# amplifier.net
KiCad netlist of a schematic drawn in Altium Designer
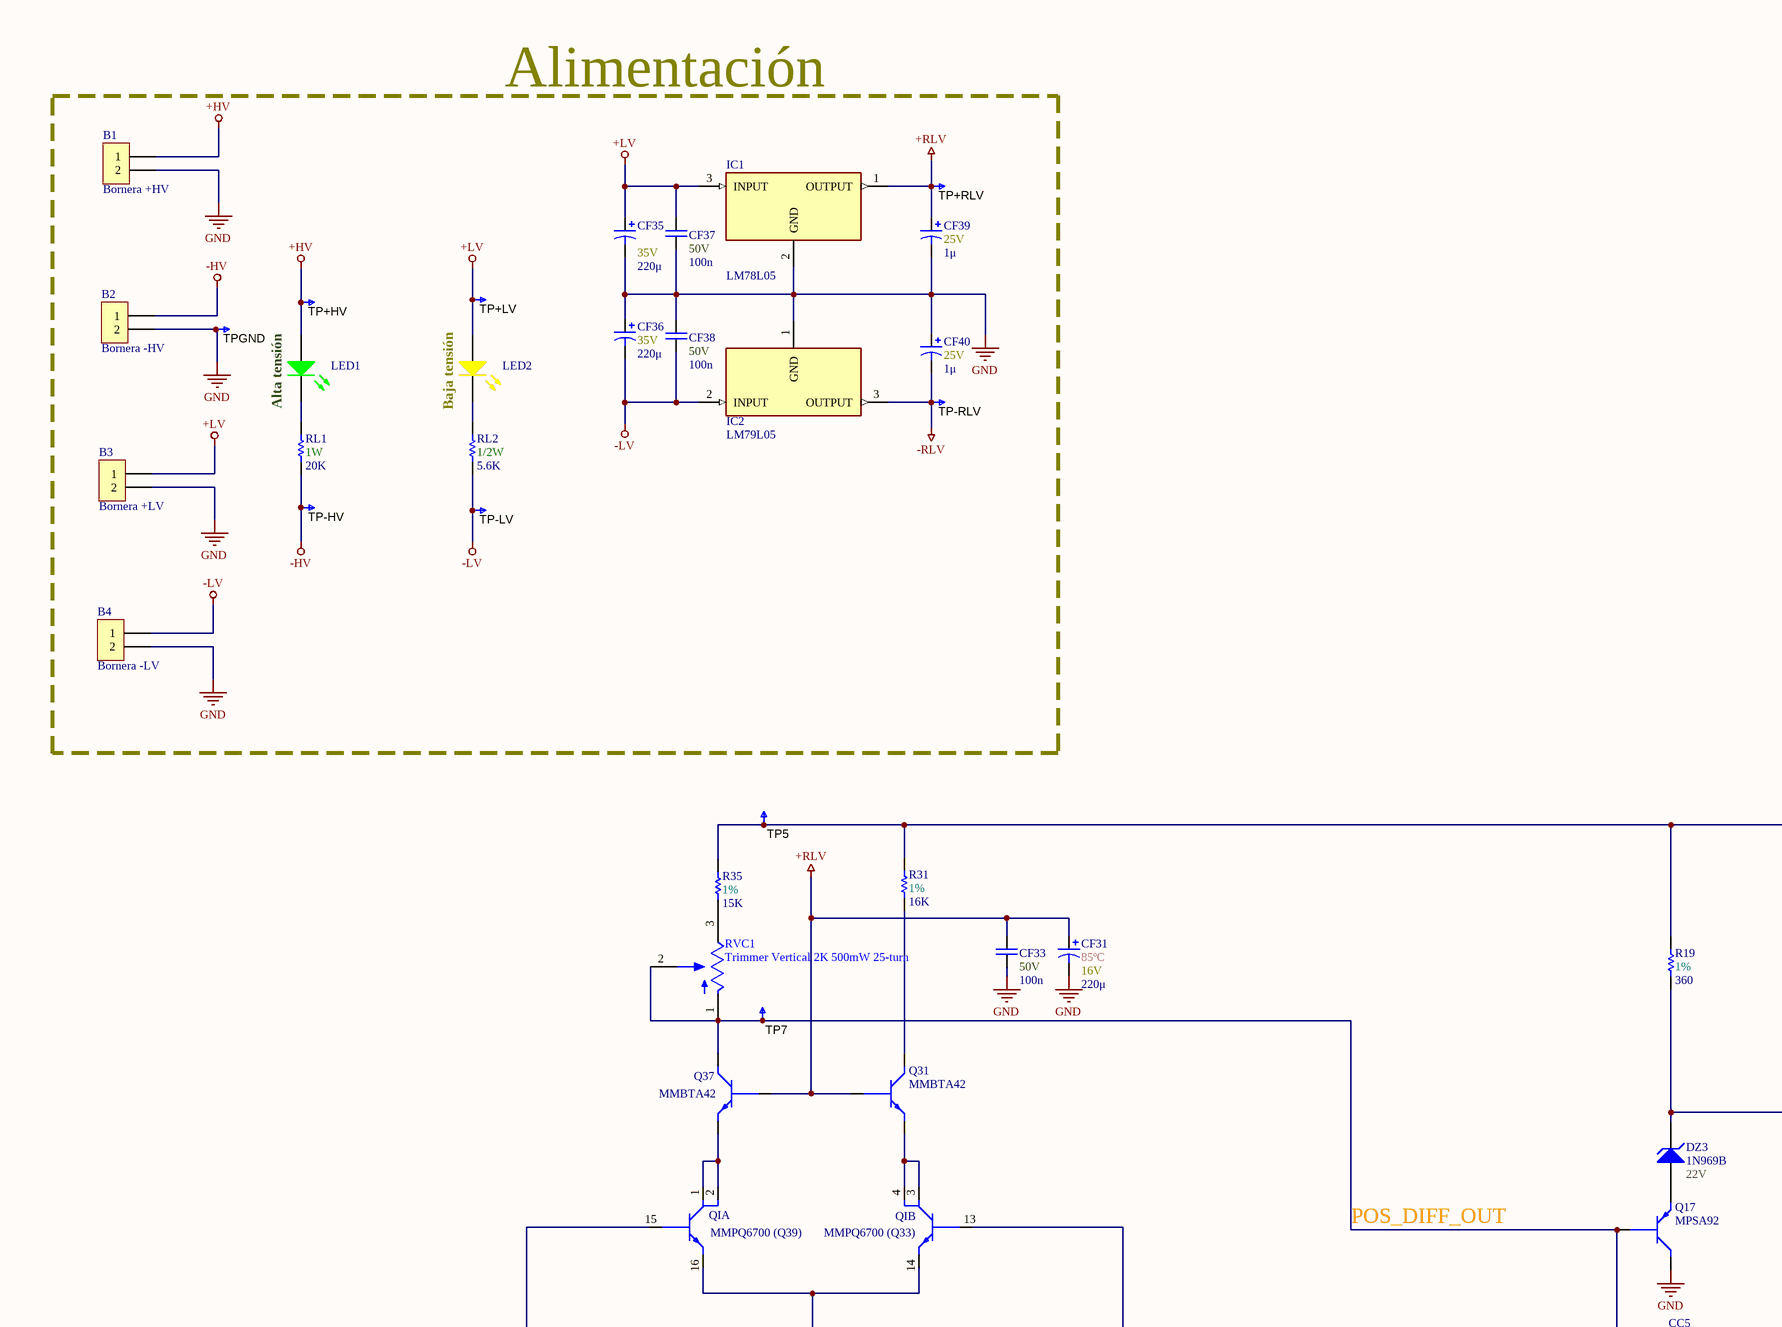
[diagram p0: amplifier.SchDoc, top left]
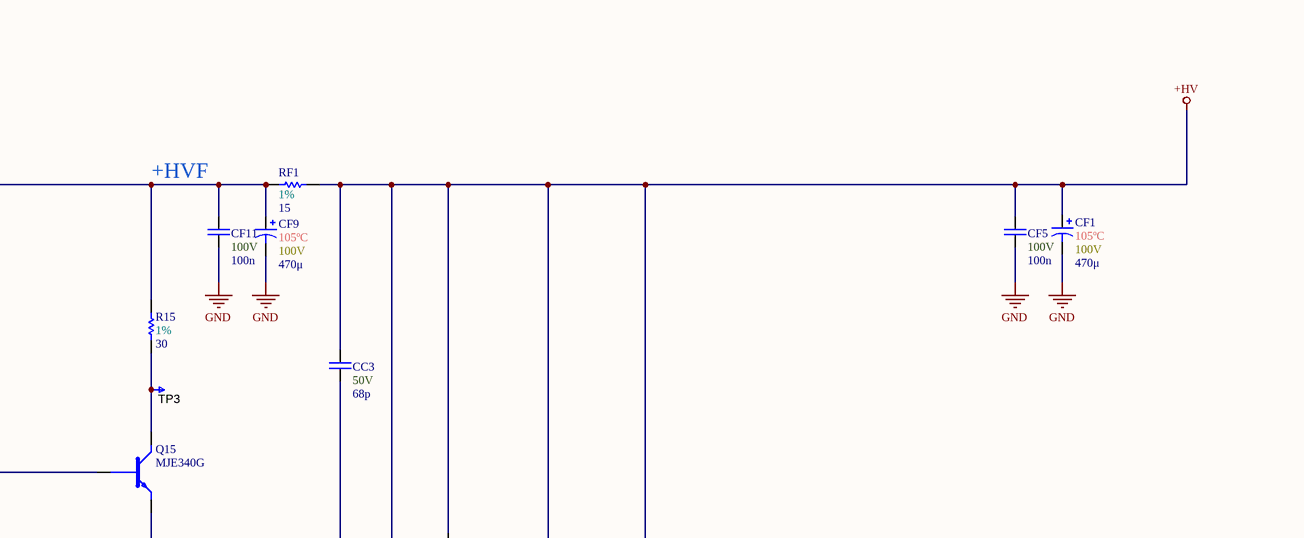
[diagram p1: amplifier.SchDoc, top right]
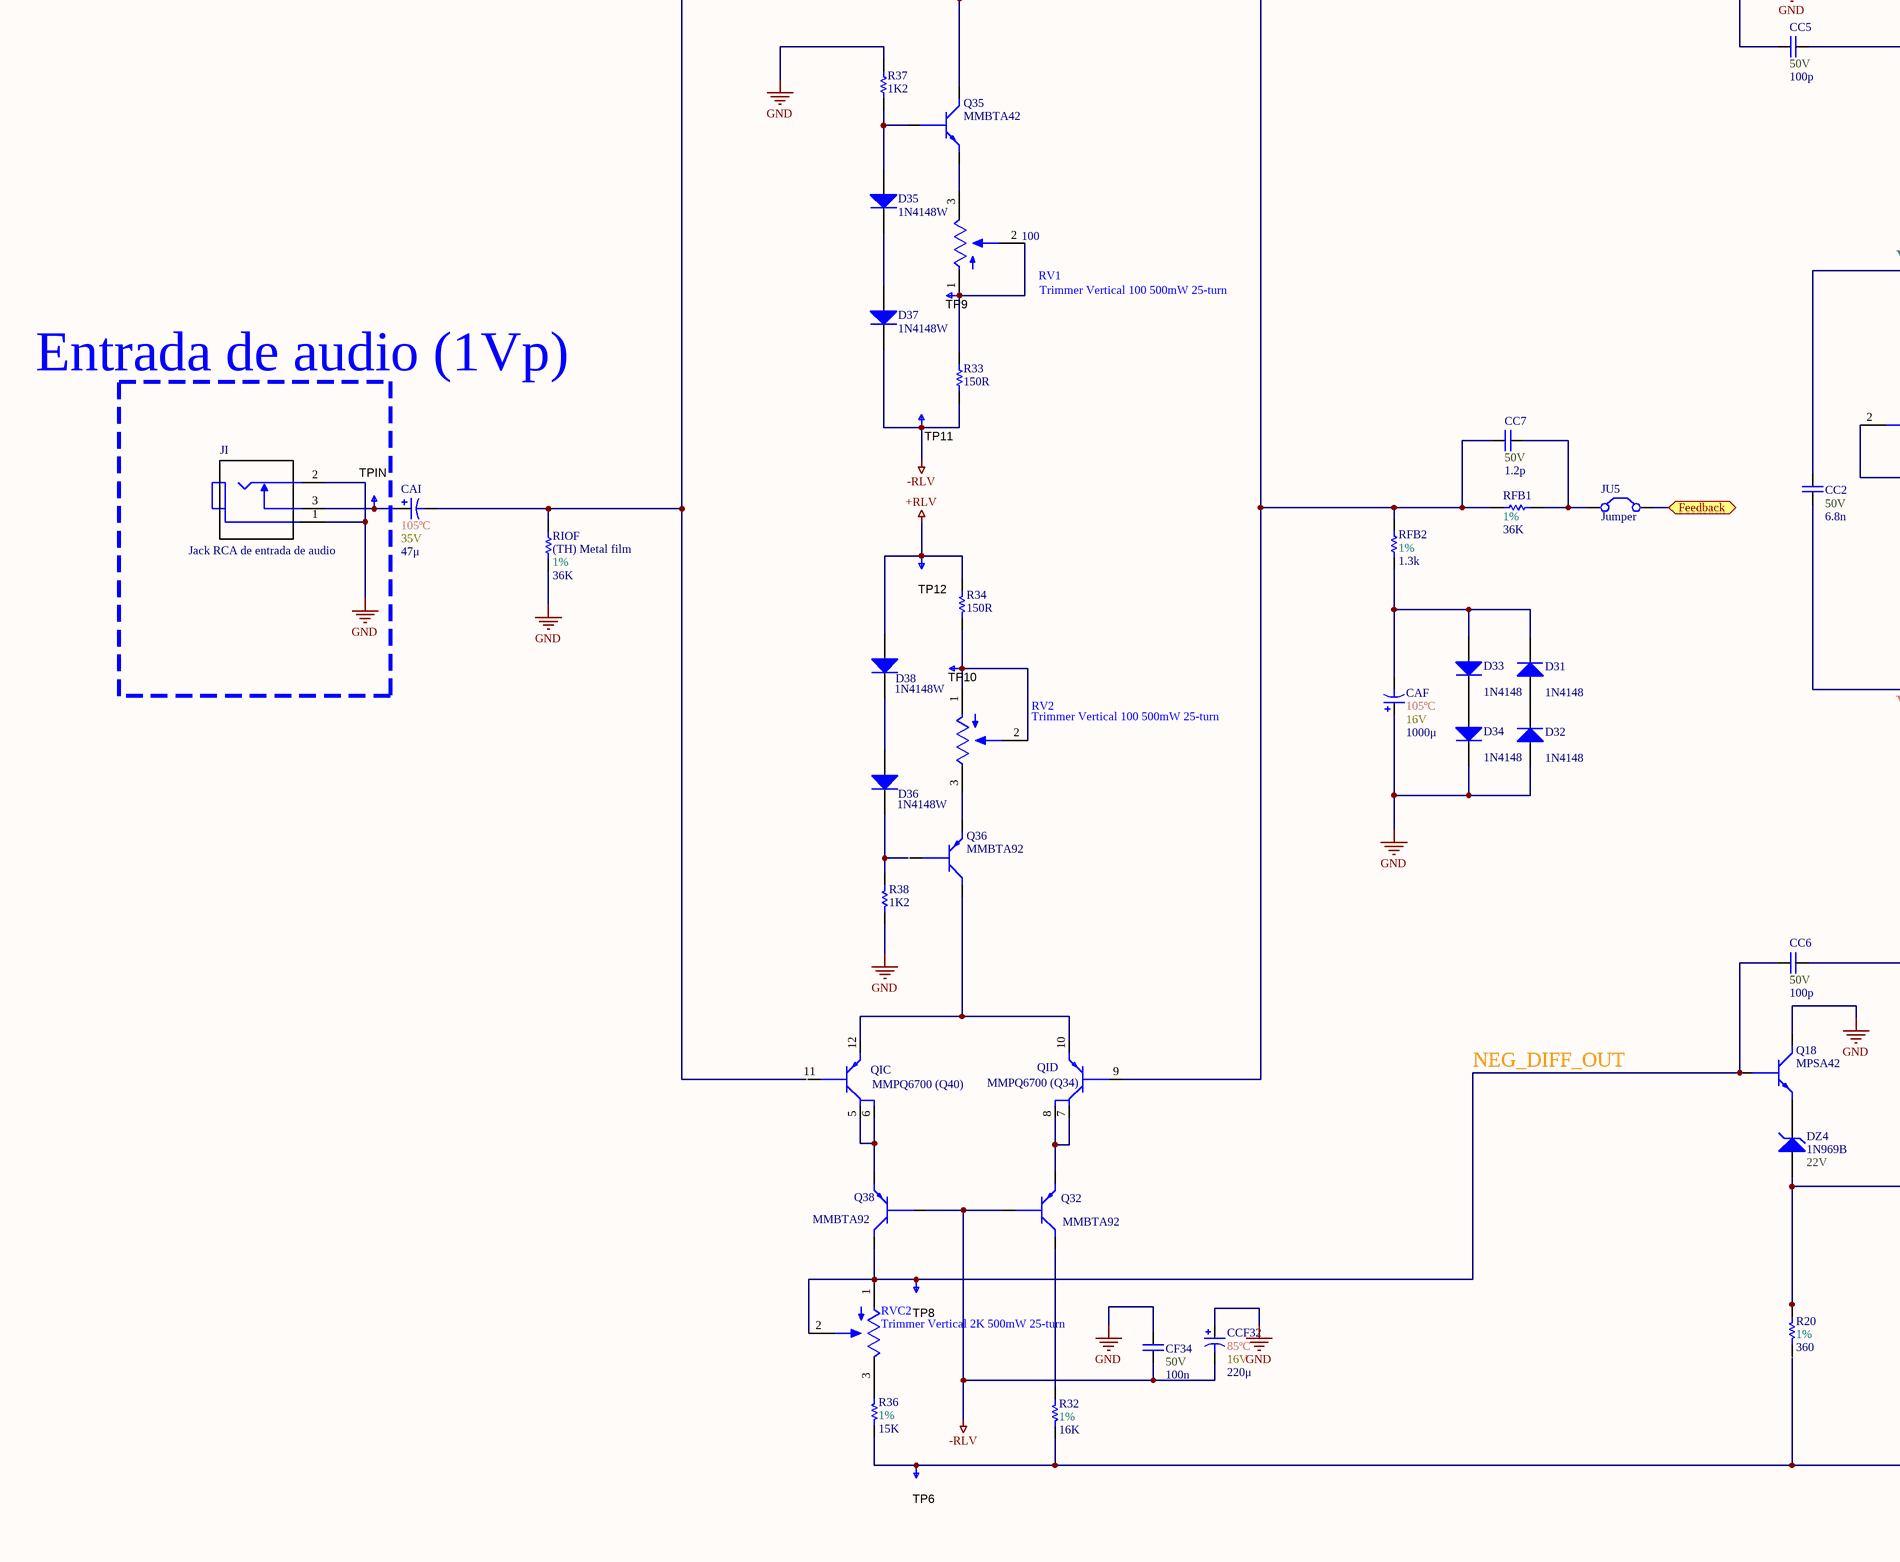
[diagram p2: amplifier.SchDoc, bottom left]
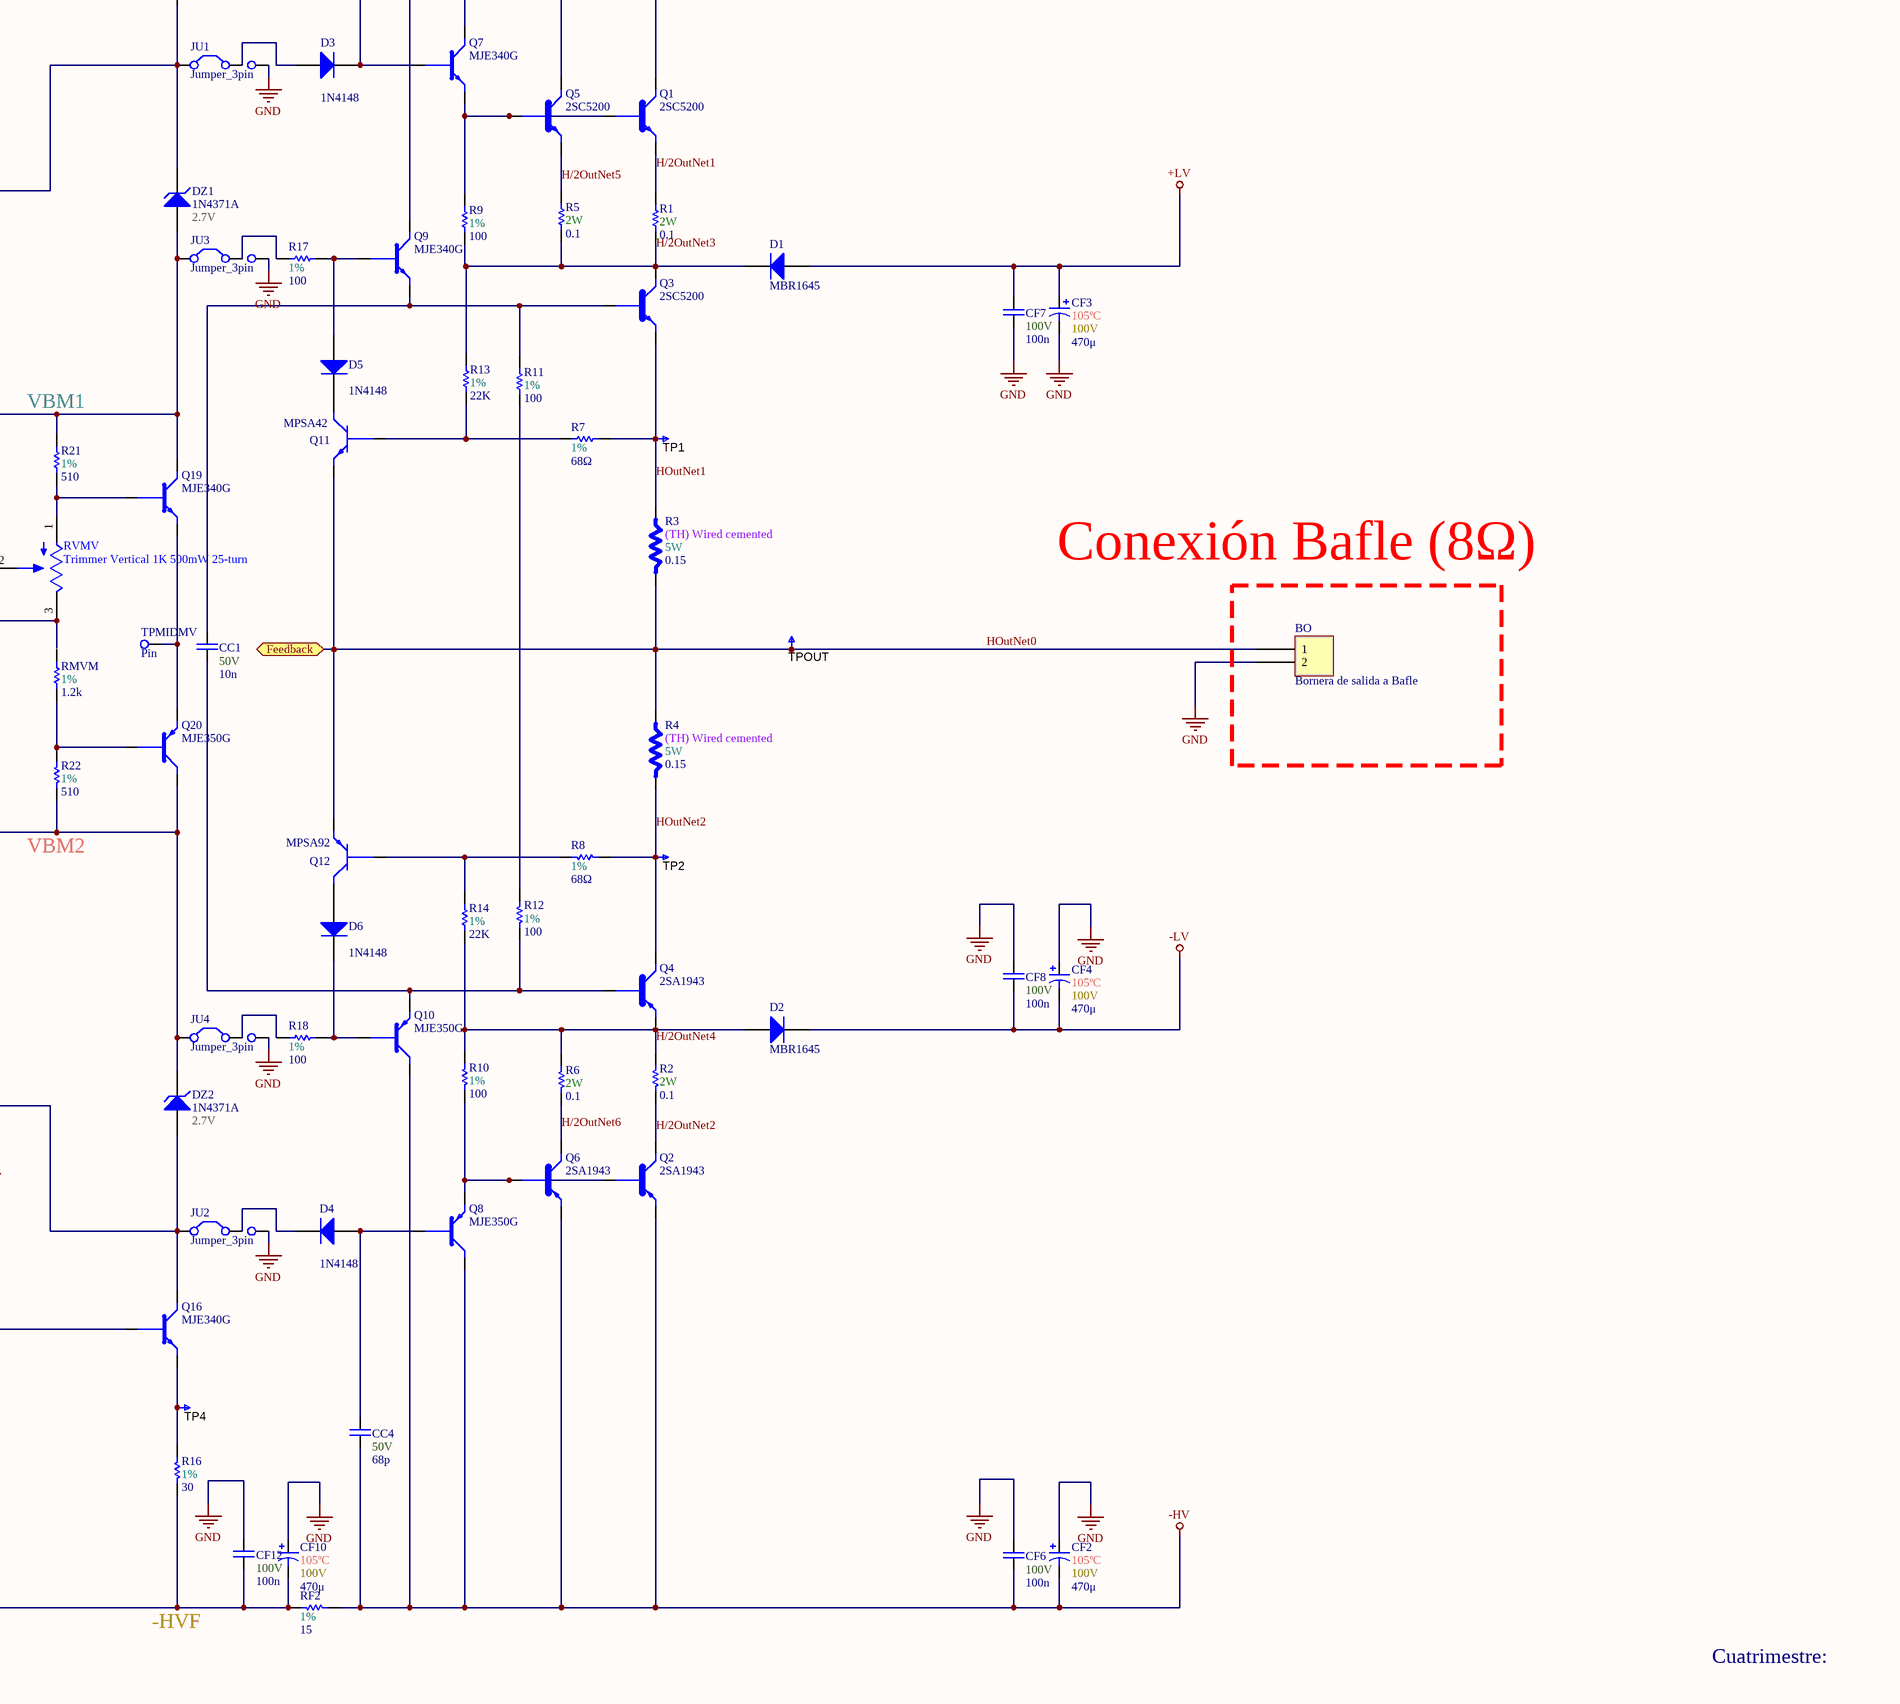
[diagram p3: amplifier.SchDoc, bottom right]

(export (version "E")
  (design (tool "Eeschema 10.0.6"))
  (components
    (comp (ref "B1")
      (value "Bornera +HV")
      (footprint "TE-C-282822-2-C-PLUGGED")
      (description "TERMI-BLOK HEADER,ASSY90 2P - serie 282822 - 5.00mm")
      (fields (field (name "MANUFACTURER") "TE Connectivity") (field (name "PARTNO") "C-282822-2-C"))
      (libsource (lib "Connectors") (part "C-282822-2-C"))
    )
    (comp (ref "B2")
      (value "Bornera -HV")
      (footprint "TE-C-282822-2-C-PLUGGED")
      (description "TERMI-BLOK HEADER,ASSY90 2P - serie 282822 - 5.00mm")
      (fields (field (name "MANUFACTURER") "TE Connectivity") (field (name "PARTNO") "C-282822-2-C"))
      (libsource (lib "Connectors") (part "C-282822-2-C"))
    )
    (comp (ref "B3")
      (value "Bornera +LV")
      (footprint "TE-C-282822-2-C-PLUGGED")
      (description "TERMI-BLOK HEADER,ASSY90 2P - serie 282822 - 5.00mm")
      (fields (field (name "MANUFACTURER") "TE Connectivity") (field (name "PARTNO") "C-282822-2-C"))
      (libsource (lib "Connectors") (part "C-282822-2-C"))
    )
    (comp (ref "B4")
      (value "Bornera -LV")
      (footprint "TE-C-282822-2-C-PLUGGED")
      (description "TERMI-BLOK HEADER,ASSY90 2P - serie 282822 - 5.00mm")
      (fields (field (name "MANUFACTURER") "TE Connectivity") (field (name "PARTNO") "C-282822-2-C"))
      (libsource (lib "Connectors") (part "C-282822-2-C"))
    )
    (comp (ref "BO")
      (value "Bornera de salida a Bafle")
      (footprint "TE 8PCV-02-006")
      (description "TE Barrier Terminal Block, 2P")
      (fields (field (name "VOLTAGE") "600V"))
      (libsource (lib "Connectors") (part "8PCV-02-006"))
    )
    (comp (ref "CAF")
      (value "1000μ")
      (footprint "Al. Electrolytic 10.0mmx17.0mmx5.0mm-CLEAN")
      (description "Aluminum Electrolytic Capacitor 1000μF 16V 20% 105º")
      (fields
        (field (name "TOLERANCE") "20%")
        (field (name "TEMPERATURE") "105ºC")
        (field (name "VOLTAGE") "16V")
        (field (name "Comment") "Al. Elect. 1000u 16V 20% 105º")
      )
      (libsource (lib "Capacitors") (part "Al. Elect. 1000u 16V 20% 105º"))
    )
    (comp (ref "CAI")
      (value "47μ")
      (footprint "Al. Electrolytic 6.3mmx11.0mmx2.5mm-CLEAN")
      (description "Aluminum Electrolytic Capacitor 47μF 35V 20% 105º")
      (fields
        (field (name "TOLERANCE") "20%")
        (field (name "TEMPERATURE") "105ºC")
        (field (name "VOLTAGE") "35V")
        (field (name "Comment") "Al. Elect. 47u 35V 20% 105º")
      )
      (libsource (lib "Capacitors") (part "Al. Elect. 47u 35V 20% 105º"))
    )
    (comp (ref "CC1")
      (value "10n")
      (footprint "Cer. pitch 5.0mm height 5.5mm")
      (description "Ceramic Capacitor 10nF 50V 10%")
      (fields
        (field (name "TOLERANCE") "10%")
        (field (name "VOLTAGE") "50V")
        (field (name "Comment") "Cer. 10n 50V 10%")
      )
      (libsource (lib "Capacitors") (part "Cer. 10n 50V 10%"))
    )
    (comp (ref "CC2")
      (value "6.8n")
      (footprint "Cer. pitch 2.5mm height 5.0mm")
      (description "Ceramic Capacitor 6.8nF 50V 10%")
      (fields
        (field (name "TOLERANCE") "10%")
        (field (name "VOLTAGE") "50V")
        (field (name "Comment") "Cer. 6.8n 50V 10%")
      )
      (libsource (lib "Capacitors") (part "Cer. 6.8n 50V 10%"))
    )
    (comp (ref "CC3")
      (value "68p")
      (footprint "Cer. pitch 5.08mm height 6.00mm")
      (description "Ceramic Capacitor 68pF 50V 10%")
      (fields
        (field (name "TOLERANCE") "10%")
        (field (name "VOLTAGE") "50V")
        (field (name "Comment") "Cer. 68p 50V 10%")
      )
      (libsource (lib "Capacitors") (part "Cer. 68p 50V 10%"))
    )
    (comp (ref "CC4")
      (value "68p")
      (footprint "Cer. pitch 5.08mm height 6.00mm")
      (description "Ceramic Capacitor 68pF 50V 10%")
      (fields
        (field (name "TOLERANCE") "10%")
        (field (name "VOLTAGE") "50V")
        (field (name "Comment") "Cer. 68p 50V 10%")
      )
      (libsource (lib "Capacitors") (part "Cer. 68p 50V 10%"))
    )
    (comp (ref "CC5")
      (value "100p")
      (footprint "Cer. pitch 5.08mm height 6.00mm")
      (description "Ceramic Capacitor 100pF 50V 10%")
      (fields
        (field (name "TOLERANCE") "10%")
        (field (name "VOLTAGE") "50V")
        (field (name "Comment") "Cer. 100p 50V 10%")
      )
      (libsource (lib "Capacitors") (part "Cer. 100p 50V 10%"))
    )
    (comp (ref "CC6")
      (value "100p")
      (footprint "Cer. pitch 5.08mm height 6.00mm")
      (description "Ceramic Capacitor 100pF 50V 10%")
      (fields
        (field (name "TOLERANCE") "10%")
        (field (name "VOLTAGE") "50V")
        (field (name "Comment") "Cer. 100p 50V 10%")
      )
      (libsource (lib "Capacitors") (part "Cer. 100p 50V 10%"))
    )
    (comp (ref "CC7")
      (value "1.2p")
      (footprint "Cer. pitch 5.08mm height 6.00mm")
      (description "Ceramic Capacitor 1.2pF 50V 10%")
      (fields
        (field (name "TOLERANCE") "10%")
        (field (name "VOLTAGE") "50V")
        (field (name "Comment") "Cer. 1.2p 50V 10%")
      )
      (libsource (lib "Capacitors") (part "Cer. 1.2p 50V 10%"))
    )
    (comp (ref "CCF32")
      (value "220μ")
      (footprint "Al. Electrolytic 6.3mmx12.0mmx2.5mm-CLEAN")
      (description "Aluminum Electrolytic Capacitor 220μF 16V 20% 85º")
      (fields
        (field (name "TOLERANCE") "20%")
        (field (name "TEMPERATURE") "85ºC")
        (field (name "VOLTAGE") "16V")
        (field (name "Comment") "Al. Elect. 220u 16V 20% 85º")
      )
      (libsource (lib "Capacitors") (part "Al. Elect. 220u 16V 20% 85º"))
    )
    (comp (ref "CF1")
      (value "470μ")
      (footprint "Al. Electrolytic 16.0mmx33.0mmx7.5mm-CLEAN")
      (description "Aluminum Electrolytic Capacitor 470μF 100V 20% 105º")
      (fields
        (field (name "TOLERANCE") "20%")
        (field (name "TEMPERATURE") "105ºC")
        (field (name "VOLTAGE") "100V")
        (field (name "Comment") "Al. Elect. 470u 100V 20% 105º")
      )
      (libsource (lib "Capacitors") (part "Al. Elect. 470u 100V 20% 105º"))
    )
    (comp (ref "CF2")
      (value "470μ")
      (footprint "Al. Electrolytic 16.0mmx33.0mmx7.5mm-CLEAN")
      (description "Aluminum Electrolytic Capacitor 470μF 100V 20% 105º")
      (fields
        (field (name "TOLERANCE") "20%")
        (field (name "TEMPERATURE") "105ºC")
        (field (name "VOLTAGE") "100V")
        (field (name "Comment") "Al. Elect. 470u 100V 20% 105º")
      )
      (libsource (lib "") (part "Al. Elect. 470u 100V 20% 105º_1"))
    )
    (comp (ref "CF3")
      (value "470μ")
      (footprint "Al. Electrolytic 16.0mmx33.0mmx7.5mm-CLEAN")
      (description "Aluminum Electrolytic Capacitor 470μF 100V 20% 105º")
      (fields
        (field (name "TOLERANCE") "20%")
        (field (name "TEMPERATURE") "105ºC")
        (field (name "VOLTAGE") "100V")
        (field (name "Comment") "Al. Elect. 470u 100V 20% 105º")
      )
      (libsource (lib "Capacitors") (part "Al. Elect. 470u 100V 20% 105º"))
    )
    (comp (ref "CF4")
      (value "470μ")
      (footprint "Al. Electrolytic 16.0mmx33.0mmx7.5mm-CLEAN")
      (description "Aluminum Electrolytic Capacitor 470μF 100V 20% 105º")
      (fields
        (field (name "TOLERANCE") "20%")
        (field (name "TEMPERATURE") "105ºC")
        (field (name "VOLTAGE") "100V")
        (field (name "Comment") "Al. Elect. 470u 100V 20% 105º")
      )
      (libsource (lib "") (part "Al. Elect. 470u 100V 20% 105º_1"))
    )
    (comp (ref "CF5")
      (value "100n")
      (footprint "Cer. pitch 5.0mm height 6.6mm")
      (description "Polyester Capacitor 100nF 100V 10%")
      (fields
        (field (name "TOLERANCE") "10%")
        (field (name "VOLTAGE") "100V")
        (field (name "Comment") "Poly. 100n 100V 10%")
      )
      (libsource (lib "Capacitors") (part "Poly. 100n 100V 10%"))
    )
    (comp (ref "CF6")
      (value "100n")
      (footprint "Cer. pitch 5.0mm height 6.6mm")
      (description "Polyester Capacitor 100nF 100V 10%")
      (fields
        (field (name "TOLERANCE") "10%")
        (field (name "VOLTAGE") "100V")
        (field (name "Comment") "Poly. 100n 100V 10%")
      )
      (libsource (lib "Capacitors") (part "Poly. 100n 100V 10%"))
    )
    (comp (ref "CF7")
      (value "100n")
      (footprint "Cer. pitch 5.0mm height 6.6mm")
      (description "Polyester Capacitor 100nF 100V 10%")
      (fields
        (field (name "TOLERANCE") "10%")
        (field (name "VOLTAGE") "100V")
        (field (name "Comment") "Poly. 100n 100V 10%")
      )
      (libsource (lib "Capacitors") (part "Poly. 100n 100V 10%"))
    )
    (comp (ref "CF8")
      (value "100n")
      (footprint "Cer. pitch 5.0mm height 6.6mm")
      (description "Polyester Capacitor 100nF 100V 10%")
      (fields
        (field (name "TOLERANCE") "10%")
        (field (name "VOLTAGE") "100V")
        (field (name "Comment") "Poly. 100n 100V 10%")
      )
      (libsource (lib "Capacitors") (part "Poly. 100n 100V 10%"))
    )
    (comp (ref "CF9")
      (value "470μ")
      (footprint "Al. Electrolytic 16.0mmx33.0mmx7.5mm-CLEAN")
      (description "Aluminum Electrolytic Capacitor 470μF 100V 20% 105º")
      (fields
        (field (name "TOLERANCE") "20%")
        (field (name "TEMPERATURE") "105ºC")
        (field (name "VOLTAGE") "100V")
        (field (name "Comment") "Al. Elect. 470u 100V 20% 105º")
      )
      (libsource (lib "Capacitors") (part "Al. Elect. 470u 100V 20% 105º"))
    )
    (comp (ref "CF10")
      (value "470μ")
      (footprint "Al. Electrolytic 16.0mmx33.0mmx7.5mm-CLEAN")
      (description "Aluminum Electrolytic Capacitor 470μF 100V 20% 105º")
      (fields
        (field (name "TOLERANCE") "20%")
        (field (name "TEMPERATURE") "105ºC")
        (field (name "VOLTAGE") "100V")
        (field (name "Comment") "Al. Elect. 470u 100V 20% 105º")
      )
      (libsource (lib "") (part "Al. Elect. 470u 100V 20% 105º_1"))
    )
    (comp (ref "CF11")
      (value "100n")
      (footprint "Cer. pitch 5.0mm height 6.6mm")
      (description "Polyester Capacitor 100nF 100V 10%")
      (fields
        (field (name "TOLERANCE") "10%")
        (field (name "VOLTAGE") "100V")
        (field (name "Comment") "Poly. 100n 100V 10%")
      )
      (libsource (lib "Capacitors") (part "Poly. 100n 100V 10%"))
    )
    (comp (ref "CF12")
      (value "100n")
      (footprint "Cer. pitch 5.0mm height 6.6mm")
      (description "Polyester Capacitor 100nF 100V 10%")
      (fields
        (field (name "TOLERANCE") "10%")
        (field (name "VOLTAGE") "100V")
        (field (name "Comment") "Poly. 100n 100V 10%")
      )
      (libsource (lib "Capacitors") (part "Poly. 100n 100V 10%"))
    )
    (comp (ref "CF31")
      (value "220μ")
      (footprint "Al. Electrolytic 6.3mmx12.0mmx2.5mm-CLEAN")
      (description "Aluminum Electrolytic Capacitor 220μF 16V 20% 85º")
      (fields
        (field (name "TOLERANCE") "20%")
        (field (name "TEMPERATURE") "85ºC")
        (field (name "VOLTAGE") "16V")
        (field (name "Comment") "Al. Elect. 220u 16V 20% 85º")
      )
      (libsource (lib "") (part "Al. Elect. 220u 16V 20% 85º_1"))
    )
    (comp (ref "CF33")
      (value "100n")
      (footprint "Cer. pitch 5.0mm height 5.5mm")
      (description "Ceramic Capacitor 100nF 50V 10%")
      (fields
        (field (name "TOLERANCE") "10%")
        (field (name "VOLTAGE") "50V")
        (field (name "Comment") "Cer. 100n 50V 10%")
      )
      (libsource (lib "Capacitors") (part "Cer. 100n 50V 10%"))
    )
    (comp (ref "CF34")
      (value "100n")
      (footprint "Cer. pitch 5.0mm height 5.5mm")
      (description "Ceramic Capacitor 100nF 50V 10%")
      (fields
        (field (name "TOLERANCE") "10%")
        (field (name "VOLTAGE") "50V")
        (field (name "Comment") "Cer. 100n 50V 10%")
      )
      (libsource (lib "Capacitors") (part "Cer. 100n 50V 10%"))
    )
    (comp (ref "CF35")
      (value "220μ")
      (footprint "Al. Electrolytic 8.0mmx13.0mmx3.5mm-CLEAN")
      (description "Aluminum Electrolytic Capacitor 220μF 35V 20% 105º")
      (fields
        (field (name "TOLERANCE") "20%")
        (field (name "VOLTAGE") "35V")
        (field (name "Comment") "Al. Elect. 220u 35V 20% 105º")
      )
      (libsource (lib "Capacitors") (part "Al. Elect. 220u 35V 20% 105º"))
    )
    (comp (ref "CF36")
      (value "220μ")
      (footprint "Al. Electrolytic 8.0mmx13.0mmx3.5mm-CLEAN")
      (description "Aluminum Electrolytic Capacitor 220μF 35V 20% 105º")
      (fields
        (field (name "TOLERANCE") "20%")
        (field (name "VOLTAGE") "35V")
        (field (name "Comment") "Al. Elect. 220u 35V 20% 105º")
      )
      (libsource (lib "Capacitors") (part "Al. Elect. 220u 35V 20% 105º"))
    )
    (comp (ref "CF37")
      (value "100n")
      (footprint "Cer. pitch 5.0mm height 5.5mm")
      (description "Ceramic Capacitor 100nF 50V 10%")
      (fields
        (field (name "TOLERANCE") "10%")
        (field (name "VOLTAGE") "50V")
        (field (name "Comment") "Cer. 100n 50V 10%")
      )
      (libsource (lib "Capacitors") (part "Cer. 100n 50V 10%"))
    )
    (comp (ref "CF38")
      (value "100n")
      (footprint "Cer. pitch 5.0mm height 5.5mm")
      (description "Ceramic Capacitor 100nF 50V 10%")
      (fields
        (field (name "TOLERANCE") "10%")
        (field (name "VOLTAGE") "50V")
        (field (name "Comment") "Cer. 100n 50V 10%")
      )
      (libsource (lib "Capacitors") (part "Cer. 100n 50V 10%"))
    )
    (comp (ref "CF39")
      (value "1μ")
      (footprint "Tantalum Electrolytic 4.5mmx8.0mmx0.254mm-CLEAN")
      (description "Tantalum Electrolytic Capacitor 1μF 25V 10%")
      (fields
        (field (name "TOLERANCE") "10%")
        (field (name "VOLTAGE") "25V")
        (field (name "Comment") "Tant. Elect. 1u 25V 10%")
      )
      (libsource (lib "Capacitors") (part "Tant. Elect. 1u 25V 10%"))
    )
    (comp (ref "CF40")
      (value "1μ")
      (footprint "Tantalum Electrolytic 4.5mmx8.0mmx0.254mm-CLEAN")
      (description "Tantalum Electrolytic Capacitor 1μF 25V 10%")
      (fields
        (field (name "TOLERANCE") "10%")
        (field (name "VOLTAGE") "25V")
        (field (name "Comment") "Tant. Elect. 1u 25V 10%")
      )
      (libsource (lib "Capacitors") (part "Tant. Elect. 1u 25V 10%"))
    )
    (comp (ref "D1")
      (value "MBR1645")
      (footprint "ONSC-TO-220-2-221B-04")
      (description "45 V, 16 A SWITCHMODE(TM) Schottky Power Rectifier, 2-Pin TO-220, Pb-Free, Tube")
      (libsource (lib "ON Semi Rectifiers") (part "MBR1645"))
    )
    (comp (ref "D2")
      (value "MBR1645")
      (footprint "ONSC-TO-220-2-221B-04")
      (description "45 V, 16 A SWITCHMODE(TM) Schottky Power Rectifier, 2-Pin TO-220, Pb-Free, Tube")
      (libsource (lib "ON Semi Rectifiers") (part "MBR1645"))
    )
    (comp (ref "D3")
      (value "1N4148")
      (footprint "DO-35-0.3mil")
      (description "FAST SWITCHING DIODE")
      (fields
        (field (name "MANUFACTURER") "ON Semiconductors")
        (field (name "POWER") "400mW")
        (field (name "PARTNUMBER") "1N4148")
      )
      (libsource (lib "ON Semi Rectifiers") (part "1N4148"))
    )
    (comp (ref "D4")
      (value "1N4148")
      (footprint "DO-35-0.3mil")
      (description "FAST SWITCHING DIODE")
      (fields
        (field (name "MANUFACTURER") "ON Semiconductors")
        (field (name "POWER") "400mW")
        (field (name "PARTNUMBER") "1N4148")
      )
      (libsource (lib "ON Semi Rectifiers") (part "1N4148"))
    )
    (comp (ref "D5")
      (value "~")
      (footprint "DO-35-0.3mil")
      (description "FAST SWITCHING DIODE")
      (fields
        (field (name "MANUFACTURER") "ON Semiconductors")
        (field (name "POWER") "400mW")
        (field (name "PARTNUMBER") "1N4148")
      )
      (libsource (lib "ON Semi Rectifiers") (part "1N4148"))
    )
    (comp (ref "D6")
      (value "~")
      (footprint "DO-35-0.3mil")
      (description "FAST SWITCHING DIODE")
      (fields
        (field (name "MANUFACTURER") "ON Semiconductors")
        (field (name "POWER") "400mW")
        (field (name "PARTNUMBER") "1N4148")
      )
      (libsource (lib "ON Semi Rectifiers") (part "1N4148"))
    )
    (comp (ref "D31")
      (value "~")
      (footprint "DO-35-0.3mil")
      (description "FAST SWITCHING DIODE")
      (fields
        (field (name "MANUFACTURER") "ON Semiconductors")
        (field (name "POWER") "400mW")
        (field (name "PARTNUMBER") "1N4148")
      )
      (libsource (lib "ON Semi Rectifiers") (part "1N4148"))
    )
    (comp (ref "D32")
      (value "~")
      (footprint "DO-35-0.3mil")
      (description "FAST SWITCHING DIODE")
      (fields
        (field (name "MANUFACTURER") "ON Semiconductors")
        (field (name "POWER") "400mW")
        (field (name "PARTNUMBER") "1N4148")
      )
      (libsource (lib "ON Semi Rectifiers") (part "1N4148"))
    )
    (comp (ref "D33")
      (value "~")
      (footprint "DO-35-0.3mil")
      (description "FAST SWITCHING DIODE")
      (fields
        (field (name "MANUFACTURER") "ON Semiconductors")
        (field (name "POWER") "400mW")
        (field (name "PARTNUMBER") "1N4148")
      )
      (libsource (lib "ON Semi Rectifiers") (part "1N4148"))
    )
    (comp (ref "D34")
      (value "~")
      (footprint "DO-35-0.3mil")
      (description "FAST SWITCHING DIODE")
      (fields
        (field (name "MANUFACTURER") "ON Semiconductors")
        (field (name "POWER") "400mW")
        (field (name "PARTNUMBER") "1N4148")
      )
      (libsource (lib "ON Semi Rectifiers") (part "1N4148"))
    )
    (comp (ref "D35")
      (value "1N4148W")
      (footprint "SOD-123")
      (description "SURFACE MOUNT FAST SWITCHING DIODE")
      (fields (field (name "MANUFACTURER") "Diodes Incorporated") (field (name "POWER") "400mW"))
      (libsource (lib "DIODES_INCROPORATED") (part "1N4148W"))
    )
    (comp (ref "D36")
      (value "1N4148W")
      (footprint "SOD-123")
      (description "SURFACE MOUNT FAST SWITCHING DIODE")
      (fields (field (name "MANUFACTURER") "Diodes Incorporated") (field (name "POWER") "400mW"))
      (libsource (lib "DIODES_INCROPORATED") (part "1N4148W"))
    )
    (comp (ref "D37")
      (value "1N4148W")
      (footprint "SOD-123")
      (description "SURFACE MOUNT FAST SWITCHING DIODE")
      (fields (field (name "MANUFACTURER") "Diodes Incorporated") (field (name "POWER") "400mW"))
      (libsource (lib "DIODES_INCROPORATED") (part "1N4148W"))
    )
    (comp (ref "D38")
      (value "1N4148W")
      (footprint "SOD-123")
      (description "SURFACE MOUNT FAST SWITCHING DIODE")
      (fields (field (name "MANUFACTURER") "Diodes Incorporated") (field (name "POWER") "400mW"))
      (libsource (lib "DIODES_INCROPORATED") (part "1N4148W"))
    )
    (comp (ref "DZ1")
      (value "1N4371A")
      (footprint "DO-35-0.3mil")
      (description "Zener Diode, 2.7V, 500mW")
      (fields
        (field (name "MANUFACTURER") "Microsemi")
        (field (name "POWER") "500mW")
        (field (name "ZV") "2.7V")
        (field (name "PUBLISHER") "Altium Limited")
      )
      (libsource (lib "MICROSEMI") (part "1N4371A"))
    )
    (comp (ref "DZ2")
      (value "1N4371A")
      (footprint "DO-35-0.3mil")
      (description "Zener Diode, 2.7V, 500mW")
      (fields
        (field (name "MANUFACTURER") "Microsemi")
        (field (name "POWER") "500mW")
        (field (name "ZV") "2.7V")
        (field (name "PUBLISHER") "Altium Limited")
      )
      (libsource (lib "MICROSEMI") (part "1N4371A"))
    )
    (comp (ref "DZ3")
      (value "1N969B")
      (footprint "DO-35-0.3mil")
      (description "Zener Diode, 22V, 500mW")
      (fields
        (field (name "MANUFACTURER") "Microsemi")
        (field (name "POWER") "500mW")
        (field (name "ZV") "22V")
        (field (name "PUBLISHER") "Altium Limited")
      )
      (libsource (lib "MICROSEMI") (part "1N969B"))
    )
    (comp (ref "DZ4")
      (value "1N969B")
      (footprint "DO-35-0.3mil")
      (description "Zener Diode, 22V, 500mW")
      (fields
        (field (name "MANUFACTURER") "Microsemi")
        (field (name "POWER") "500mW")
        (field (name "ZV") "22V")
        (field (name "PUBLISHER") "Altium Limited")
      )
      (libsource (lib "MICROSEMI") (part "1N969B"))
    )
    (comp (ref "IC1")
      (value "LM78L05")
      (footprint "TO-92-1")
      (description "5V fixed regulator - 100mA")
      (fields (field (name "MANUFACTURER_PART_NUMBER") "LM7805"))
      (libsource (lib "FIXED_REGULATORS") (part "LM78L05"))
    )
    (comp (ref "IC2")
      (value "LM79L05")
      (footprint "TO-92-1")
      (description "-5V fixed regulator - 100mA")
      (fields (field (name "MANUFACTURER_PART_NUMBER") "LM7805"))
      (libsource (lib "FIXED_REGULATORS") (part "LM79L05"))
    )
    (comp (ref "JI")
      (value "Jack RCA de entrada de audio")
      (footprint "*SWITCHCRAFT_PJRAN1X1U01X")
      (description "Conn Phono Jack F 3 POS Solder RA Thru-Hole 3 Terminal 1 Port")
      (fields (field (name "MP") "PJRAN1X1U01X") (field (name "MF") "Switchcraft"))
      (libsource (lib "Connectors") (part "PJRAN1X1U01X"))
    )
    (comp (ref "JU1")
      (value "Jumper_3pin")
      (footprint "Jumper 200mil 3 pin")
      (description "Jumper Wire")
      (fields (field (name "PUBLISHER") "Altium Limited"))
      (libsource (lib "Test Points and Jumpers") (part "Jumper_3pin"))
    )
    (comp (ref "JU2")
      (value "Jumper_3pin")
      (footprint "Jumper 200mil 3 pin")
      (description "Jumper Wire")
      (fields (field (name "PUBLISHER") "Altium Limited"))
      (libsource (lib "Test Points and Jumpers") (part "Jumper_3pin"))
    )
    (comp (ref "JU3")
      (value "Jumper_3pin")
      (footprint "Jumper 200mil 3 pin")
      (description "Jumper Wire")
      (fields (field (name "PUBLISHER") "Altium Limited"))
      (libsource (lib "Test Points and Jumpers") (part "Jumper_3pin"))
    )
    (comp (ref "JU4")
      (value "Jumper_3pin")
      (footprint "Jumper 200mil 3 pin")
      (description "Jumper Wire")
      (fields (field (name "PUBLISHER") "Altium Limited"))
      (libsource (lib "Test Points and Jumpers") (part "Jumper_3pin"))
    )
    (comp (ref "JU5")
      (value "Jumper")
      (footprint "Jumper 200mil 2 pin")
      (description "Jumper Wire")
      (fields (field (name "PUBLISHER") "Altium Limited"))
      (libsource (lib "Test Points and Jumpers") (part "Jumper"))
    )
    (comp (ref "LED1")
      (value "Alta tensión")
      (footprint "LED_5MM_GREEN")
      (description "Typical LED (GREEN)")
      (fields (field (name "PUBLISHER") "Altium Limited"))
      (libsource (lib "GENERIC_LED") (part "LED (GREEN)"))
    )
    (comp (ref "LED2")
      (value "Baja tensión")
      (footprint "LED_5MM_YELLOW")
      (description "Typical LED (YELLOW)")
      (fields (field (name "PUBLISHER") "Altium Limited"))
      (libsource (lib "GENERIC_LED") (part "LED (YELLOW)"))
    )
    (comp (ref "Q1")
      (value "2SC5200")
      (footprint "TO-264-3")
      (description "Transistor GP BJT NPN 230V 15A 3-Pin_3+Tab_ TO-264 Tube")
      (fields (field (name "MANUFACTURER") "Toshiba") (field (name "POWER") "150W"))
      (libsource (lib "TOSHIBA") (part "2SC5200"))
    )
    (comp (ref "Q2")
      (value "2SA1943")
      (footprint "TO-264-3")
      (description "Transistor GP BJT PNP 230V 15A 3-Pin_3+Tab_ TO-264 Tube")
      (fields (field (name "MANUFACTURER") "Toshiba") (field (name "POWER") "150W"))
      (libsource (lib "TOSHIBA") (part "2SA1943"))
    )
    (comp (ref "Q3")
      (value "2SC5200")
      (footprint "TO-264-3")
      (description "Transistor GP BJT NPN 230V 15A 3-Pin_3+Tab_ TO-264 Tube")
      (fields (field (name "MANUFACTURER") "Toshiba") (field (name "POWER") "150W"))
      (libsource (lib "TOSHIBA") (part "2SC5200"))
    )
    (comp (ref "Q4")
      (value "2SA1943")
      (footprint "TO-264-3")
      (description "Transistor GP BJT PNP 230V 15A 3-Pin_3+Tab_ TO-264 Tube")
      (fields (field (name "MANUFACTURER") "Toshiba") (field (name "POWER") "150W"))
      (libsource (lib "TOSHIBA") (part "2SA1943"))
    )
    (comp (ref "Q5")
      (value "2SC5200")
      (footprint "TO-264-3")
      (description "Transistor GP BJT NPN 230V 15A 3-Pin_3+Tab_ TO-264 Tube")
      (fields (field (name "MANUFACTURER") "Toshiba") (field (name "POWER") "150W"))
      (libsource (lib "TOSHIBA") (part "2SC5200"))
    )
    (comp (ref "Q6")
      (value "2SA1943")
      (footprint "TO-264-3")
      (description "Transistor GP BJT PNP 230V 15A 3-Pin_3+Tab_ TO-264 Tube")
      (fields (field (name "MANUFACTURER") "Toshiba") (field (name "POWER") "150W"))
      (libsource (lib "TOSHIBA") (part "2SA1943"))
    )
    (comp (ref "Q7")
      (value "MJE340G")
      (footprint "TO-225")
      (description "Plastic Medium-Power NPN Silicon Transistor, 300 VOLTS, 0.5 AMPERE, 20 WATTS")
      (fields (field (name "MANUFACTURER") "ON Semiconductor") (field (name "POWER") "20W"))
      (libsource (lib "ON Semi Transistors") (part "MJE340G"))
    )
    (comp (ref "Q8")
      (value "MJE350G")
      (footprint "TO-225")
      (description "Plastic Medium-Power PNP Silicon Transistor, 300 VOLTS, 0.5 AMPERE, 20 WATTS")
      (fields (field (name "MANUFACTURER") "ON Semiconductor") (field (name "POWER") "20W"))
      (libsource (lib "ON Semi Transistors") (part "MJE350G"))
    )
    (comp (ref "Q9")
      (value "MJE340G")
      (footprint "TO-225")
      (description "Plastic Medium-Power NPN Silicon Transistor, 300 VOLTS, 0.5 AMPERE, 20 WATTS")
      (fields (field (name "MANUFACTURER") "ON Semiconductor") (field (name "POWER") "20W"))
      (libsource (lib "ON Semi Transistors") (part "MJE340G"))
    )
    (comp (ref "Q10")
      (value "MJE350G")
      (footprint "TO-225")
      (description "Plastic Medium-Power PNP Silicon Transistor, 300 VOLTS, 0.5 AMPERE, 20 WATTS")
      (fields (field (name "MANUFACTURER") "ON Semiconductor") (field (name "POWER") "20W"))
      (libsource (lib "ON Semi Transistors") (part "MJE350G"))
    )
    (comp (ref "Q11")
      (value "MPSA42")
      (footprint "TO-92-1")
      (description "High Voltage NPN Bipolar Transistor")
      (fields (field (name "MANUFACTURER") "ON Semiconductor") (field (name "PARTNUMBER") "MJE340G"))
      (libsource (lib "ON Semi Transistors") (part "MPSA42"))
    )
    (comp (ref "Q12")
      (value "MPSA92")
      (footprint "TO-92-1")
      (description "High Voltage PNP Bipolar Transistor")
      (fields (field (name "MANUFACTURER") "ON Semiconductor") (field (name "PARTNUMBER") "MJE340G"))
      (libsource (lib "ON Semi Transistors") (part "MPSA92"))
    )
    (comp (ref "Q15")
      (value "MJE340G")
      (footprint "TO-225")
      (description "Plastic Medium-Power NPN Silicon Transistor, 300 VOLTS, 0.5 AMPERE, 20 WATTS")
      (fields (field (name "MANUFACTURER") "ON Semiconductor") (field (name "POWER") "20W"))
      (libsource (lib "ON Semi Transistors") (part "MJE340G"))
    )
    (comp (ref "Q16")
      (value "MJE340G")
      (footprint "TO-225")
      (description "Plastic Medium-Power NPN Silicon Transistor, 300 VOLTS, 0.5 AMPERE, 20 WATTS")
      (fields (field (name "MANUFACTURER") "ON Semiconductor") (field (name "POWER") "20W"))
      (libsource (lib "ON Semi Transistors") (part "MJE340G"))
    )
    (comp (ref "Q17")
      (value "MPSA92")
      (footprint "TO-92-1")
      (description "High Voltage PNP Bipolar Transistor")
      (fields (field (name "MANUFACTURER") "ON Semiconductor") (field (name "PARTNUMBER") "MJE340G"))
      (libsource (lib "ON Semi Transistors") (part "MPSA92"))
    )
    (comp (ref "Q18")
      (value "MPSA42")
      (footprint "TO-92-1")
      (description "High Voltage NPN Bipolar Transistor")
      (fields (field (name "MANUFACTURER") "ON Semiconductor") (field (name "PARTNUMBER") "MJE340G"))
      (libsource (lib "ON Semi Transistors") (part "MPSA42"))
    )
    (comp (ref "Q19")
      (value "MJE340G")
      (footprint "TO-225")
      (description "Plastic Medium-Power NPN Silicon Transistor, 300 VOLTS, 0.5 AMPERE, 20 WATTS")
      (fields (field (name "MANUFACTURER") "ON Semiconductor") (field (name "POWER") "20W"))
      (libsource (lib "ON Semi Transistors") (part "MJE340G"))
    )
    (comp (ref "Q20")
      (value "MJE350G")
      (footprint "TO-225")
      (description "Plastic Medium-Power PNP Silicon Transistor, 300 VOLTS, 0.5 AMPERE, 20 WATTS")
      (fields (field (name "MANUFACTURER") "ON Semiconductor") (field (name "POWER") "20W"))
      (libsource (lib "ON Semi Transistors") (part "MJE350G"))
    )
    (comp (ref "Q31")
      (value "MMBTA42")
      (footprint "SOT-23")
      (description "High Voltage NPN Bipolar Transistor")
      (fields (field (name "MANUFACTURER") "ON Semiconductor") (field (name "PARTNUMBER") "MJE340G"))
      (libsource (lib "ON Semi Transistors") (part "MMBTA42"))
    )
    (comp (ref "Q32")
      (value "MMBTA92")
      (footprint "SOT-23")
      (description "High Voltage PNP Bipolar Transistor")
      (fields (field (name "MANUFACTURER") "ON Semiconductor") (field (name "PARTNUMBER") "MJE340G"))
      (libsource (lib "ON Semi Transistors") (part "MMBTA92"))
    )
    (comp (ref "Q35")
      (value "MMBTA42")
      (footprint "SOT-23")
      (description "High Voltage NPN Bipolar Transistor")
      (fields (field (name "MANUFACTURER") "ON Semiconductor") (field (name "PARTNUMBER") "MJE340G"))
      (libsource (lib "ON Semi Transistors") (part "MMBTA42"))
    )
    (comp (ref "Q36")
      (value "MMBTA92")
      (footprint "SOT-23")
      (description "High Voltage PNP Bipolar Transistor")
      (fields (field (name "MANUFACTURER") "ON Semiconductor") (field (name "PARTNUMBER") "MJE340G"))
      (libsource (lib "ON Semi Transistors") (part "MMBTA92"))
    )
    (comp (ref "Q37")
      (value "MMBTA42")
      (footprint "SOT-23")
      (description "High Voltage NPN Bipolar Transistor")
      (fields (field (name "MANUFACTURER") "ON Semiconductor") (field (name "PARTNUMBER") "MJE340G"))
      (libsource (lib "ON Semi Transistors") (part "MMBTA42"))
    )
    (comp (ref "Q38")
      (value "MMBTA92")
      (footprint "SOT-23")
      (description "High Voltage PNP Bipolar Transistor")
      (fields (field (name "MANUFACTURER") "ON Semiconductor") (field (name "PARTNUMBER") "MJE340G"))
      (libsource (lib "ON Semi Transistors") (part "MMBTA92"))
    )
    (comp (ref "QI")
      (value "MMPQ6700 (Q34)")
      (footprint "SOIC-16L")
      (description "Quad NPN and PNP General-Purpose Amplifier")
      (fields (field (name "MANUFACTURER") "ON Semiconductor") (field (name "PARTNUMBER") "MMPQ6700"))
      (libsource (lib "ON Semi Transistors") (part "MMPQ6700"))
    )
    (comp (ref "R1")
      (value "0.1")
      (footprint "AXIAL-0.6-E24-2W-0.1")
      (description "Resistor 0.1Ω 2W 5%")
      (fields
        (field (name "TOLERANCE") "5%")
        (field (name "POWER") "2W")
        (field (name "Comment") "Resistor 0.1 2W 5%")
      )
      (libsource (lib "Resistors") (part "Resistor 0.1 2W 5%"))
    )
    (comp (ref "R2")
      (value "0.1")
      (footprint "AXIAL-0.6-E24-2W-0.1")
      (description "Resistor 0.1Ω 2W 5%")
      (fields
        (field (name "TOLERANCE") "5%")
        (field (name "POWER") "2W")
        (field (name "Comment") "Resistor 0.1 2W 5%")
      )
      (libsource (lib "Resistors") (part "Resistor 0.1 2W 5%"))
    )
    (comp (ref "R3")
      (value "0.15")
      (footprint "Cemented resistor 0.15 5W 5%")
      (description "Cemented resistor 0.15Ω 5% 5W")
      (fields
        (field (name "TOLERANCE") "5%")
        (field (name "TYPE") "(TH) Wired cemented")
        (field (name "POWER") "5W")
        (field (name "Comment") "Cemented resistor 0.15 5W 5%")
      )
      (libsource (lib "Resistors") (part "Cemented resistor 0.15 5W 5%"))
    )
    (comp (ref "R4")
      (value "0.15")
      (footprint "Cemented resistor 0.15 5W 5%")
      (description "Cemented resistor 0.15Ω 5% 5W")
      (fields
        (field (name "TOLERANCE") "5%")
        (field (name "TYPE") "(TH) Wired cemented")
        (field (name "POWER") "5W")
        (field (name "Comment") "Cemented resistor 0.15 5W 5%")
      )
      (libsource (lib "Resistors") (part "Cemented resistor 0.15 5W 5%"))
    )
    (comp (ref "R5")
      (value "0.1")
      (footprint "AXIAL-0.6-E24-2W-0.1")
      (description "Resistor 0.1Ω 2W 5%")
      (fields
        (field (name "TOLERANCE") "5%")
        (field (name "POWER") "2W")
        (field (name "Comment") "Resistor 0.1 2W 5%")
      )
      (libsource (lib "Resistors") (part "Resistor 0.1 2W 5%"))
    )
    (comp (ref "R6")
      (value "0.1")
      (footprint "AXIAL-0.6-E24-2W-0.1")
      (description "Resistor 0.1Ω 2W 5%")
      (fields
        (field (name "TOLERANCE") "5%")
        (field (name "POWER") "2W")
        (field (name "Comment") "Resistor 0.1 2W 5%")
      )
      (libsource (lib "Resistors") (part "Resistor 0.1 2W 5%"))
    )
    (comp (ref "R7")
      (value "68Ω")
      (footprint "AXIAL-0.4-E24-0_25W-68-1%")
      (description "Resistor 68Ω 1/4W 1%")
      (fields
        (field (name "POWER") "1/4W")
        (field (name "TOLERANCE") "1%")
        (field (name "Comment") "Resistor 68 1/4W 1%")
      )
      (libsource (lib "Resistors") (part "Resistor 68 1/4W 1%"))
    )
    (comp (ref "R8")
      (value "68Ω")
      (footprint "AXIAL-0.4-E24-0_25W-68-1%")
      (description "Resistor 68Ω 1/4W 1%")
      (fields
        (field (name "POWER") "1/4W")
        (field (name "TOLERANCE") "1%")
        (field (name "Comment") "Resistor 68 1/4W 1%")
      )
      (libsource (lib "Resistors") (part "Resistor 68 1/4W 1%"))
    )
    (comp (ref "R9")
      (value "100")
      (footprint "AXIAL-0.4-E24-0_25W-100-1%")
      (description "Resistor 100Ω 1/4W 1%")
      (fields
        (field (name "POWER") "1/4W")
        (field (name "TOLERANCE") "1%")
        (field (name "Comment") "Resistor 100 1/4W 1%")
      )
      (libsource (lib "Resistors") (part "Resistor 100 1/4W 1%"))
    )
    (comp (ref "R10")
      (value "100")
      (footprint "AXIAL-0.4-E24-0_25W-100-1%")
      (description "Resistor 100Ω 1/4W 1%")
      (fields
        (field (name "POWER") "1/4W")
        (field (name "TOLERANCE") "1%")
        (field (name "Comment") "Resistor 100 1/4W 1%")
      )
      (libsource (lib "Resistors") (part "Resistor 100 1/4W 1%"))
    )
    (comp (ref "R11")
      (value "100")
      (footprint "AXIAL-0.4-E24-0_25W-100-1%")
      (description "Resistor 100Ω 1/4W 1%")
      (fields
        (field (name "POWER") "1/4W")
        (field (name "TOLERANCE") "1%")
        (field (name "Comment") "Resistor 100 1/4W 1%")
      )
      (libsource (lib "Resistors") (part "Resistor 100 1/4W 1%"))
    )
    (comp (ref "R12")
      (value "100")
      (footprint "AXIAL-0.4-E24-0_25W-100-1%")
      (description "Resistor 100Ω 1/4W 1%")
      (fields
        (field (name "POWER") "1/4W")
        (field (name "TOLERANCE") "1%")
        (field (name "Comment") "Resistor 100 1/4W 1%")
      )
      (libsource (lib "Resistors") (part "Resistor 100 1/4W 1%"))
    )
    (comp (ref "R13")
      (value "22K")
      (footprint "AXIAL-0.4-E24-0_25W-22k-1%")
      (description "Resistor 22KΩ 1/4W 1%")
      (fields
        (field (name "POWER") "1/4W")
        (field (name "TOLERANCE") "1%")
        (field (name "Comment") "Resistor 22K 1/4W 1%")
      )
      (libsource (lib "Resistors") (part "Resistor 22K 1/4W 1%"))
    )
    (comp (ref "R14")
      (value "22K")
      (footprint "AXIAL-0.4-E24-0_25W-22k-1%")
      (description "Resistor 22KΩ 1/4W 1%")
      (fields
        (field (name "POWER") "1/4W")
        (field (name "TOLERANCE") "1%")
        (field (name "Comment") "Resistor 22K 1/4W 1%")
      )
      (libsource (lib "Resistors") (part "Resistor 22K 1/4W 1%"))
    )
    (comp (ref "R15")
      (value "30")
      (footprint "AXIAL-0.4-E24-0_25W-30-1%")
      (description "Resistor 30Ω 1/4W 1%")
      (fields
        (field (name "POWER") "1/4W")
        (field (name "TOLERANCE") "1%")
        (field (name "Comment") "Resistor 30 1/4W 1%")
      )
      (libsource (lib "Resistors") (part "Resistor 30 1/4W 1%"))
    )
    (comp (ref "R16")
      (value "30")
      (footprint "AXIAL-0.4-E24-0_25W-30-1%")
      (description "Resistor 30Ω 1/4W 1%")
      (fields
        (field (name "POWER") "1/4W")
        (field (name "TOLERANCE") "1%")
        (field (name "Comment") "Resistor 30 1/4W 1%")
      )
      (libsource (lib "Resistors") (part "Resistor 30 1/4W 1%"))
    )
    (comp (ref "R17")
      (value "100")
      (footprint "AXIAL-0.4-E24-0_25W-100-1%")
      (description "Resistor 100Ω 1/4W 1%")
      (fields
        (field (name "POWER") "1/4W")
        (field (name "TOLERANCE") "1%")
        (field (name "Comment") "Resistor 100 1/4W 1%")
      )
      (libsource (lib "Resistors") (part "Resistor 100 1/4W 1%"))
    )
    (comp (ref "R18")
      (value "100")
      (footprint "AXIAL-0.4-E24-0_25W-100-1%")
      (description "Resistor 100Ω 1/4W 1%")
      (fields
        (field (name "POWER") "1/4W")
        (field (name "TOLERANCE") "1%")
        (field (name "Comment") "Resistor 100 1/4W 1%")
      )
      (libsource (lib "Resistors") (part "Resistor 100 1/4W 1%"))
    )
    (comp (ref "R19")
      (value "360")
      (footprint "AXIAL-0.4-E24-0_25W-360-1%")
      (description "Resistor 360Ω 1/4W 1%")
      (fields
        (field (name "POWER") "1/4W")
        (field (name "TOLERANCE") "1%")
        (field (name "Comment") "Resistor 360 1/4W 1%")
      )
      (libsource (lib "Resistors") (part "Resistor 360 1/4W 1%"))
    )
    (comp (ref "R20")
      (value "360")
      (footprint "AXIAL-0.4-E24-0_25W-360-1%")
      (description "Resistor 360Ω 1/4W 1%")
      (fields
        (field (name "POWER") "1/4W")
        (field (name "TOLERANCE") "1%")
        (field (name "Comment") "Resistor 360 1/4W 1%")
      )
      (libsource (lib "Resistors") (part "Resistor 360 1/4W 1%"))
    )
    (comp (ref "R21")
      (value "510")
      (footprint "AXIAL-0.4-E24-0_25W-510-1%")
      (description "Resistor 510Ω 1/4W 1%")
      (fields
        (field (name "POWER") "1/4W")
        (field (name "TOLERANCE") "1%")
        (field (name "Comment") "Resistor 510 1/4W 1%")
      )
      (libsource (lib "Resistors") (part "Resistor 510 1/4W 1%"))
    )
    (comp (ref "R22")
      (value "510")
      (footprint "AXIAL-0.4-E24-0_25W-510-1%")
      (description "Resistor 510Ω 1/4W 1%")
      (fields
        (field (name "POWER") "1/4W")
        (field (name "TOLERANCE") "1%")
        (field (name "Comment") "Resistor 510 1/4W 1%")
      )
      (libsource (lib "Resistors") (part "Resistor 510 1/4W 1%"))
    )
    (comp (ref "R31")
      (value "16K")
      (footprint "AXIAL-0.4-E24-0_25W-16k-1%")
      (description "Resistor 16KΩ 1/4W 1%")
      (fields
        (field (name "POWER") "1/4W")
        (field (name "TOLERANCE") "1%")
        (field (name "Comment") "Resistor 16K 1/4W 1%")
      )
      (libsource (lib "Resistors") (part "Resistor 16K 1/4W 1%"))
    )
    (comp (ref "R32")
      (value "16K")
      (footprint "AXIAL-0.4-E24-0_25W-16k-1%")
      (description "Resistor 16KΩ 1/4W 1%")
      (fields
        (field (name "POWER") "1/4W")
        (field (name "TOLERANCE") "1%")
        (field (name "Comment") "Resistor 16K 1/4W 1%")
      )
      (libsource (lib "Resistors") (part "Resistor 16K 1/4W 1%"))
    )
    (comp (ref "R33")
      (value "150R")
      (footprint "RES_SM0805_YAGEORC_N")
      (description "RES 150R SM0805 YAGEO RC_L")
      (fields
        (field (name "MANUFACTURER") "Yageo")
        (field (name "MANUFACTURER PART NUMBER") "RC0805FR-07150RL")
      )
      (libsource (lib "Yageo_SMD_passives_") (part "RC0805FR-07150RL"))
    )
    (comp (ref "R34")
      (value "150R")
      (footprint "RES_SM0805_YAGEORC_N")
      (description "RES 150R SM0805 YAGEO RC_L")
      (fields
        (field (name "MANUFACTURER") "Yageo")
        (field (name "MANUFACTURER PART NUMBER") "RC0805FR-07150RL")
      )
      (libsource (lib "Yageo_SMD_passives_") (part "RC0805FR-07150RL"))
    )
    (comp (ref "R35")
      (value "15K")
      (footprint "AXIAL-0.4-E24-0_25W-15k-1%")
      (description "Resistor 15KΩ 1/4W 1%")
      (fields
        (field (name "POWER") "1/4W")
        (field (name "TOLERANCE") "1%")
        (field (name "Comment") "Resistor 15K 1/4W 1%")
      )
      (libsource (lib "Resistors") (part "Resistor 15K 1/4W 1%"))
    )
    (comp (ref "R36")
      (value "15K")
      (footprint "AXIAL-0.4-E24-0_25W-15k-1%")
      (description "Resistor 15KΩ 1/4W 1%")
      (fields
        (field (name "POWER") "1/4W")
        (field (name "TOLERANCE") "1%")
        (field (name "Comment") "Resistor 15K 1/4W 1%")
      )
      (libsource (lib "Resistors") (part "Resistor 15K 1/4W 1%"))
    )
    (comp (ref "R37")
      (value "1K2")
      (footprint "RES_SM0603_YAGEORC_N")
      (description "RES 1K2 SM0603 YAGEO RC_L")
      (fields
        (field (name "MANUFACTURER") "Yageo")
        (field (name "MANUFACTURER PART NUMBER") "RC0603FR-071K2L")
      )
      (libsource (lib "Yageo_SMD_passives_") (part "RC0603FR-071K2L"))
    )
    (comp (ref "R38")
      (value "1K2")
      (footprint "RES_SM0603_YAGEORC_N")
      (description "RES 1K2 SM0603 YAGEO RC_L")
      (fields
        (field (name "MANUFACTURER") "Yageo")
        (field (name "MANUFACTURER PART NUMBER") "RC0603FR-071K2L")
      )
      (libsource (lib "Yageo_SMD_passives_") (part "RC0603FR-071K2L"))
    )
    (comp (ref "RF1")
      (value "15")
      (footprint "AXIAL-0.4-E24-0_25W-15-1%")
      (description "Resistor 15Ω 1/4W 1%")
      (fields
        (field (name "POWER") "1/4W")
        (field (name "TOLERANCE") "1%")
        (field (name "Comment") "Resistor 15 1/4W 1%")
      )
      (libsource (lib "Resistors") (part "Resistor 15 1/4W 1%"))
    )
    (comp (ref "RF2")
      (value "15")
      (footprint "AXIAL-0.4-E24-0_25W-15-1%")
      (description "Resistor 15Ω 1/4W 1%")
      (fields
        (field (name "POWER") "1/4W")
        (field (name "TOLERANCE") "1%")
        (field (name "Comment") "Resistor 15 1/4W 1%")
      )
      (libsource (lib "Resistors") (part "Resistor 15 1/4W 1%"))
    )
    (comp (ref "RFB1")
      (value "36K")
      (footprint "AXIAL-0.4-E24-0_25W-36k-1%")
      (description "Resistor 36KΩ 1/4W 1%")
      (fields
        (field (name "POWER") "1/4W")
        (field (name "TOLERANCE") "1%")
        (field (name "Comment") "Resistor 36K 1/4W 1%")
      )
      (libsource (lib "Resistors") (part "Resistor 36K 1/4W 1%"))
    )
    (comp (ref "RFB2")
      (value "1.3k")
      (footprint "AXIAL-0.4-E24-0_25W-1.3k-1%")
      (description "Resistor 1.3kΩ 1/4W 1%")
      (fields
        (field (name "POWER") "1/4W")
        (field (name "TOLERANCE") "1%")
        (field (name "Comment") "Resistor 1.3k 1/4W 1%")
      )
      (libsource (lib "Resistors") (part "Resistor 1.3k 1/4W 1%"))
    )
    (comp (ref "RIOF")
      (value "36K")
      (footprint "AXIAL-0.4-E24-0_25W-36k-1%")
      (description "Resistor 36KΩ 1/4W 1%")
      (fields
        (field (name "POWER") "1/4W")
        (field (name "TYPE") "(TH) Metal film")
        (field (name "TOLERANCE") "1%")
        (field (name "Comment") "Resistor 36K 1/4W 1%")
      )
      (libsource (lib "Resistors") (part "Resistor 36K 1/4W 1%"))
    )
    (comp (ref "RL1")
      (value "20K")
      (footprint "AXIAL-0.6-E24-1W-20K")
      (description "Resistor 20KΩ 1W 5%")
      (fields
        (field (name "TOLERANCE") "5%")
        (field (name "POWER") "1W")
        (field (name "Comment") "Resistor 20K 1W 5%")
      )
      (libsource (lib "Resistors") (part "Resistor 20K 1W 5%"))
    )
    (comp (ref "RL2")
      (value "5.6K")
      (footprint "AXIAL-0.5-E24-0_5W-5.6K")
      (description "Resistor 5.6KΩ 1/2W 5%")
      (fields
        (field (name "TOLERANCE") "5%")
        (field (name "POWER") "1/2W")
        (field (name "Comment") "Resistor 5.6K 1/2W 5%")
      )
      (libsource (lib "Resistors") (part "Resistor 5.6K 1/2W 5%"))
    )
    (comp (ref "RMVM")
      (value "1.2k")
      (footprint "AXIAL-0.4-E24-0_25W-1.2k-1%")
      (description "Resistor 1.2kΩ 1/4W 1%")
      (fields
        (field (name "POWER") "1/4W")
        (field (name "TOLERANCE") "1%")
        (field (name "Comment") "Resistor 1.2k 1/4W 1%")
      )
      (libsource (lib "Resistors") (part "Resistor 1.2k 1/4W 1%"))
    )
    (comp (ref "RV1")
      (value "Trimmer Vertical 100 500mW 25-turn")
      (footprint "POT_3296W")
      (fields (field (name "TOLERANCE") "±10%") (field (name "ALTIUM_VALUE") "100"))
      (libsource (lib "Resistors") (part "RES_TRIMMER_100_25T_VERTICAL"))
    )
    (comp (ref "RV2")
      (value "Trimmer Vertical 100 500mW 25-turn")
      (footprint "POT_3296W")
      (fields (field (name "TOLERANCE") "±10%"))
      (libsource (lib "Resistors") (part "RES_TRIMMER_100_25T_VERTICAL"))
    )
    (comp (ref "RVC1")
      (value "Trimmer Vertical 2K 500mW 25-turn")
      (footprint "POT_3296W")
      (fields (field (name "TOLERANCE") "±10%"))
      (libsource (lib "Resistors") (part "RES_TRIMMER_2K_25T_VERTICAL"))
    )
    (comp (ref "RVC2")
      (value "Trimmer Vertical 2K 500mW 25-turn")
      (footprint "POT_3296W")
      (fields (field (name "TOLERANCE") "±10%"))
      (libsource (lib "Resistors") (part "RES_TRIMMER_2K_25T_VERTICAL"))
    )
    (comp (ref "RVMV")
      (value "Trimmer Vertical 1K 500mW 25-turn")
      (footprint "POT_3296W")
      (fields (field (name "TOLERANCE") "±10%"))
      (libsource (lib "Resistors") (part "RES_TRIMMER_1K_25T_VERTICAL"))
    )
    (comp (ref "TP+HV")
      (value "TESTPOINT_THT")
      (footprint "TP-THT-MULTI")
      (description "Test Point PCB mount Multi-purpose Black")
      (fields (field (name "PBL PART NUMBER") "3100-xxx"))
      (libsource (lib "Test Points and Jumpers") (part "TESTPOINT_THT"))
    )
    (comp (ref "TP+LV")
      (value "TESTPOINT_THT")
      (footprint "TP-THT-MULTI")
      (description "Test Point PCB mount Multi-purpose Black")
      (fields (field (name "PBL PART NUMBER") "3100-xxx"))
      (libsource (lib "Test Points and Jumpers") (part "TESTPOINT_THT"))
    )
    (comp (ref "TP+RLV")
      (value "TESTPOINT_THT")
      (footprint "TP-THT-MULTI")
      (description "Test Point PCB mount Multi-purpose Black")
      (fields (field (name "PBL PART NUMBER") "3100-xxx"))
      (libsource (lib "Test Points and Jumpers") (part "TESTPOINT_THT"))
    )
    (comp (ref "TP-HV")
      (value "TESTPOINT_THT")
      (footprint "TP-THT-MULTI")
      (description "Test Point PCB mount Multi-purpose Black")
      (fields (field (name "PBL PART NUMBER") "3100-xxx"))
      (libsource (lib "Test Points and Jumpers") (part "TESTPOINT_THT"))
    )
    (comp (ref "TP-LV")
      (value "TESTPOINT_THT")
      (footprint "TP-THT-MULTI")
      (description "Test Point PCB mount Multi-purpose Black")
      (fields (field (name "PBL PART NUMBER") "3100-xxx"))
      (libsource (lib "Test Points and Jumpers") (part "TESTPOINT_THT"))
    )
    (comp (ref "TP-RLV")
      (value "TESTPOINT_THT")
      (footprint "TP-THT-MULTI")
      (description "Test Point PCB mount Multi-purpose Black")
      (fields (field (name "PBL PART NUMBER") "3100-xxx"))
      (libsource (lib "Test Points and Jumpers") (part "TESTPOINT_THT"))
    )
    (comp (ref "TP1")
      (value "TESTPOINT_THT")
      (footprint "TP-THT-MULTI")
      (description "Test Point PCB mount Multi-purpose Black")
      (fields (field (name "PBL PART NUMBER") "3100-xxx"))
      (libsource (lib "Test Points and Jumpers") (part "TESTPOINT_THT"))
    )
    (comp (ref "TP2")
      (value "TESTPOINT_THT")
      (footprint "TP-THT-MULTI")
      (description "Test Point PCB mount Multi-purpose Black")
      (fields (field (name "PBL PART NUMBER") "3100-xxx"))
      (libsource (lib "Test Points and Jumpers") (part "TESTPOINT_THT"))
    )
    (comp (ref "TP3")
      (value "TESTPOINT_THT")
      (footprint "TP-THT-MULTI")
      (description "Test Point PCB mount Multi-purpose Black")
      (fields (field (name "PBL PART NUMBER") "3100-xxx"))
      (libsource (lib "Test Points and Jumpers") (part "TESTPOINT_THT"))
    )
    (comp (ref "TP4")
      (value "TESTPOINT_THT")
      (footprint "TP-THT-MULTI")
      (description "Test Point PCB mount Multi-purpose Black")
      (fields (field (name "PBL PART NUMBER") "3100-xxx"))
      (libsource (lib "Test Points and Jumpers") (part "TESTPOINT_THT"))
    )
    (comp (ref "TP5")
      (value "TESTPOINT_THT")
      (footprint "TP-THT-MULTI")
      (description "Test Point PCB mount Multi-purpose Black")
      (fields (field (name "PBL PART NUMBER") "3100-xxx"))
      (libsource (lib "Test Points and Jumpers") (part "TESTPOINT_THT"))
    )
    (comp (ref "TP6")
      (value "TESTPOINT_THT")
      (footprint "TP-THT-MULTI")
      (description "Test Point PCB mount Multi-purpose Black")
      (fields (field (name "PBL PART NUMBER") "3100-xxx"))
      (libsource (lib "Test Points and Jumpers") (part "TESTPOINT_THT"))
    )
    (comp (ref "TP7")
      (value "TESTPOINT_THT")
      (footprint "TP-THT-MULTI")
      (description "Test Point PCB mount Multi-purpose Black")
      (fields (field (name "PBL PART NUMBER") "3100-xxx"))
      (libsource (lib "Test Points and Jumpers") (part "TESTPOINT_THT"))
    )
    (comp (ref "TP8")
      (value "TESTPOINT_THT")
      (footprint "TP-THT-MULTI")
      (description "Test Point PCB mount Multi-purpose Black")
      (fields (field (name "PBL PART NUMBER") "3100-xxx"))
      (libsource (lib "Test Points and Jumpers") (part "TESTPOINT_THT"))
    )
    (comp (ref "TP9")
      (value "TESTPOINT_THT")
      (footprint "TP-THT-MULTI")
      (description "Test Point PCB mount Multi-purpose Black")
      (fields (field (name "PBL PART NUMBER") "3100-xxx"))
      (libsource (lib "Test Points and Jumpers") (part "TESTPOINT_THT"))
    )
    (comp (ref "TP10")
      (value "TESTPOINT_THT")
      (footprint "TP-THT-MULTI")
      (description "Test Point PCB mount Multi-purpose Black")
      (fields (field (name "PBL PART NUMBER") "3100-xxx"))
      (libsource (lib "Test Points and Jumpers") (part "TESTPOINT_THT"))
    )
    (comp (ref "TP11")
      (value "TESTPOINT_THT")
      (footprint "TP-THT-MULTI")
      (description "Test Point PCB mount Multi-purpose Black")
      (fields (field (name "PBL PART NUMBER") "3100-xxx"))
      (libsource (lib "Test Points and Jumpers") (part "TESTPOINT_THT"))
    )
    (comp (ref "TP12")
      (value "TESTPOINT_THT")
      (footprint "TP-THT-MULTI")
      (description "Test Point PCB mount Multi-purpose Black")
      (fields (field (name "PBL PART NUMBER") "3100-xxx"))
      (libsource (lib "Test Points and Jumpers") (part "TESTPOINT_THT"))
    )
    (comp (ref "TPGND")
      (value "TESTPOINT_THT")
      (footprint "TP-THT-MULTI")
      (description "Test Point PCB mount Multi-purpose Black")
      (fields (field (name "PBL PART NUMBER") "3100-xxx"))
      (libsource (lib "Test Points and Jumpers") (part "TESTPOINT_THT"))
    )
    (comp (ref "TPIN")
      (value "TESTPOINT_THT")
      (footprint "TP-THT-MULTI")
      (description "Test Point PCB mount Multi-purpose Black")
      (fields (field (name "PBL PART NUMBER") "3100-xxx"))
      (libsource (lib "Test Points and Jumpers") (part "TESTPOINT_THT"))
    )
    (comp (ref "TPMIDMV")
      (value "Pin")
      (footprint "Jumper 200mil 1 pin")
      (description "Jumper Wire")
      (fields (field (name "PUBLISHER") "Altium Limited"))
      (libsource (lib "Test Points and Jumpers") (part "Pin"))
    )
    (comp (ref "TPOUT")
      (value "TESTPOINT_THT")
      (footprint "TP-THT-MULTI")
      (description "Test Point PCB mount Multi-purpose Black")
      (fields (field (name "PBL PART NUMBER") "3100-xxx"))
      (libsource (lib "Test Points and Jumpers") (part "TESTPOINT_THT"))
    )
  )
  (nets
    (net (code "1") (name "+HV") (class "Default")
      (node (ref "B1") (pin "1") (pinfunction "1_1") (pintype "power_in"))
      (node (ref "CC3") (pin "2") (pinfunction "2_2") (pintype "passive"))
      (node (ref "CF1") (pin "1") (pinfunction "1_1") (pintype "passive"))
      (node (ref "CF5") (pin "2") (pinfunction "2_2") (pintype "passive"))
      (node (ref "LED1") (pin "A") (pinfunction "A_A") (pintype "passive"))
      (node (ref "Q1") (pin "2") (pinfunction "C_2") (pintype "passive"))
      (node (ref "Q5") (pin "2") (pinfunction "C_2") (pintype "passive"))
      (node (ref "Q7") (pin "2") (pinfunction "C_2") (pintype "passive"))
      (node (ref "Q9") (pin "2") (pinfunction "C_2") (pintype "passive"))
      (node (ref "RF1") (pin "2") (pinfunction "2_2") (pintype "passive"))
      (node (ref "TP+HV") (pin "1") (pintype "passive"))
    )
    (net (code "2") (name "+LV") (class "Default")
      (node (ref "B3") (pin "1") (pinfunction "1_1") (pintype "power_in"))
      (node (ref "CF3") (pin "1") (pinfunction "1_1") (pintype "passive"))
      (node (ref "CF35") (pin "1") (pinfunction "1_1") (pintype "passive"))
      (node (ref "CF37") (pin "2") (pinfunction "2_2") (pintype "passive"))
      (node (ref "CF7") (pin "2") (pinfunction "2_2") (pintype "passive"))
      (node (ref "D1") (pin "3") (pinfunction "A_3") (pintype "passive"))
      (node (ref "IC1") (pin "3") (pinfunction "INPUT_3") (pintype "input"))
      (node (ref "LED2") (pin "A") (pinfunction "A_A") (pintype "passive"))
      (node (ref "TP+LV") (pin "1") (pintype "passive"))
    )
    (net (code "3") (name "+RLV") (class "Default")
      (node (ref "CF31") (pin "1") (pinfunction "1_1") (pintype "passive"))
      (node (ref "CF33") (pin "2") (pinfunction "2_2") (pintype "passive"))
      (node (ref "CF39") (pin "1") (pinfunction "1_1") (pintype "passive"))
      (node (ref "D38") (pin "2") (pinfunction "A_2") (pintype "passive"))
      (node (ref "IC1") (pin "1") (pinfunction "OUTPUT_1") (pintype "output"))
      (node (ref "Q31") (pin "1") (pinfunction "B_1") (pintype "passive"))
      (node (ref "Q37") (pin "1") (pinfunction "B_1") (pintype "passive"))
      (node (ref "R34") (pin "1") (pintype "passive"))
      (node (ref "TP+RLV") (pin "1") (pintype "passive"))
      (node (ref "TP12") (pin "1") (pintype "passive"))
    )
    (net (code "4") (name "-HV") (class "Default")
      (node (ref "B2") (pin "1") (pinfunction "1_1") (pintype "power_in"))
      (node (ref "CC4") (pin "1") (pinfunction "1_1") (pintype "passive"))
      (node (ref "CF2") (pin "2") (pinfunction "2_2") (pintype "passive"))
      (node (ref "CF6") (pin "1") (pinfunction "1_1") (pintype "passive"))
      (node (ref "Q10") (pin "2") (pinfunction "C_2") (pintype "passive"))
      (node (ref "Q2") (pin "3") (pinfunction "E_3") (pintype "passive"))
      (node (ref "Q6") (pin "3") (pinfunction "E_3") (pintype "passive"))
      (node (ref "Q8") (pin "2") (pinfunction "C_2") (pintype "passive"))
      (node (ref "RF2") (pin "2") (pinfunction "2_2") (pintype "passive"))
      (node (ref "RL1") (pin "1") (pinfunction "1_1") (pintype "passive"))
      (node (ref "TP-HV") (pin "1") (pintype "passive"))
    )
    (net (code "5") (name "-LV") (class "Default")
      (node (ref "B4") (pin "1") (pinfunction "1_1") (pintype "power_in"))
      (node (ref "CF36") (pin "2") (pinfunction "2_2") (pintype "passive"))
      (node (ref "CF38") (pin "1") (pinfunction "1_1") (pintype "passive"))
      (node (ref "CF4") (pin "2") (pinfunction "2_2") (pintype "passive"))
      (node (ref "CF8") (pin "1") (pinfunction "1_1") (pintype "passive"))
      (node (ref "D2") (pin "1") (pinfunction "K_1") (pintype "passive"))
      (node (ref "IC2") (pin "2") (pinfunction "INPUT_2") (pintype "input"))
      (node (ref "RL2") (pin "1") (pinfunction "1_1") (pintype "passive"))
      (node (ref "TP-LV") (pin "1") (pintype "passive"))
    )
    (net (code "6") (name "-RLV") (class "Default")
      (node (ref "CCF32") (pin "2") (pinfunction "2_2") (pintype "passive"))
      (node (ref "CF34") (pin "2") (pinfunction "2_2") (pintype "passive"))
      (node (ref "CF40") (pin "2") (pinfunction "2_2") (pintype "passive"))
      (node (ref "D37") (pin "1") (pinfunction "K_1") (pintype "passive"))
      (node (ref "IC2") (pin "3") (pinfunction "OUTPUT_3") (pintype "output"))
      (node (ref "Q32") (pin "1") (pinfunction "B_1") (pintype "passive"))
      (node (ref "Q38") (pin "1") (pinfunction "B_1") (pintype "passive"))
      (node (ref "R33") (pin "1") (pintype "passive"))
      (node (ref "TP-RLV") (pin "1") (pintype "passive"))
      (node (ref "TP11") (pin "1") (pintype "passive"))
    )
    (net (code "7") (name "/+HVF") (class "Default")
      (node (ref "CF11") (pin "2") (pinfunction "2_2") (pintype "passive"))
      (node (ref "CF9") (pin "1") (pinfunction "1_1") (pintype "passive"))
      (node (ref "R15") (pin "2") (pinfunction "2_2") (pintype "passive"))
      (node (ref "R19") (pin "2") (pinfunction "2_2") (pintype "passive"))
      (node (ref "R31") (pin "2") (pinfunction "2_2") (pintype "passive"))
      (node (ref "R35") (pin "2") (pinfunction "2_2") (pintype "passive"))
      (node (ref "RF1") (pin "1") (pinfunction "1_1") (pintype "passive"))
      (node (ref "TP5") (pin "1") (pintype "passive"))
    )
    (net (code "8") (name "/-HVF") (class "Default")
      (node (ref "CF10") (pin "2") (pinfunction "2_2") (pintype "passive"))
      (node (ref "CF12") (pin "2") (pinfunction "2_2") (pintype "passive"))
      (node (ref "R16") (pin "2") (pinfunction "2_2") (pintype "passive"))
      (node (ref "R32") (pin "2") (pinfunction "2_2") (pintype "passive"))
      (node (ref "R36") (pin "2") (pinfunction "2_2") (pintype "passive"))
      (node (ref "RF2") (pin "1") (pinfunction "1_1") (pintype "passive"))
      (node (ref "TP6") (pin "1") (pintype "passive"))
    )
    (net (code "9") (name "/HOutNet0") (class "Default")
      (node (ref "BO") (pin "1") (pinfunction "1_1") (pintype "passive"))
      (node (ref "JU5") (pin "2") (pinfunction "C2_2") (pintype "passive"))
      (node (ref "Q11") (pin "1") (pinfunction "E_1") (pintype "passive"))
      (node (ref "Q12") (pin "1") (pinfunction "E_1") (pintype "passive"))
      (node (ref "R3") (pin "2") (pinfunction "2_2") (pintype "passive"))
      (node (ref "R4") (pin "1") (pinfunction "1_1") (pintype "passive"))
      (node (ref "TPOUT") (pin "1") (pintype "passive"))
    )
    (net (code "10") (name "/HOutNet1") (class "Default")
      (node (ref "Q3") (pin "3") (pinfunction "E_3") (pintype "passive"))
      (node (ref "R3") (pin "1") (pinfunction "1_1") (pintype "passive"))
      (node (ref "R7") (pin "2") (pinfunction "2_2") (pintype "passive"))
      (node (ref "TP1") (pin "1") (pintype "passive"))
    )
    (net (code "11") (name "/HOutNet2") (class "Default")
      (node (ref "Q4") (pin "2") (pinfunction "C_2") (pintype "passive"))
      (node (ref "R4") (pin "2") (pinfunction "2_2") (pintype "passive"))
      (node (ref "R8") (pin "1") (pinfunction "1_1") (pintype "passive"))
      (node (ref "TP2") (pin "1") (pintype "passive"))
    )
    (net (code "12") (name "/H{slash}2OutNet1") (class "Default")
      (node (ref "Q1") (pin "3") (pinfunction "E_3") (pintype "passive"))
      (node (ref "R1") (pin "2") (pinfunction "2_2") (pintype "passive"))
    )
    (net (code "13") (name "/H{slash}2OutNet2") (class "Default")
      (node (ref "Q2") (pin "2") (pinfunction "C_2") (pintype "passive"))
      (node (ref "R2") (pin "1") (pinfunction "1_1") (pintype "passive"))
    )
    (net (code "14") (name "/H{slash}2OutNet3") (class "Default")
      (node (ref "D1") (pin "1") (pinfunction "K_1") (pintype "passive"))
      (node (ref "Q3") (pin "2") (pinfunction "C_2") (pintype "passive"))
      (node (ref "R1") (pin "1") (pinfunction "1_1") (pintype "passive"))
      (node (ref "R13") (pin "2") (pinfunction "2_2") (pintype "passive"))
      (node (ref "R5") (pin "1") (pinfunction "1_1") (pintype "passive"))
      (node (ref "R9") (pin "1") (pinfunction "1_1") (pintype "passive"))
    )
    (net (code "15") (name "/H{slash}2OutNet4") (class "Default")
      (node (ref "D2") (pin "3") (pinfunction "A_3") (pintype "passive"))
      (node (ref "Q4") (pin "3") (pinfunction "E_3") (pintype "passive"))
      (node (ref "R10") (pin "2") (pinfunction "2_2") (pintype "passive"))
      (node (ref "R14") (pin "1") (pinfunction "1_1") (pintype "passive"))
      (node (ref "R2") (pin "2") (pinfunction "2_2") (pintype "passive"))
      (node (ref "R6") (pin "2") (pinfunction "2_2") (pintype "passive"))
    )
    (net (code "16") (name "/H{slash}2OutNet5") (class "Default")
      (node (ref "Q5") (pin "3") (pinfunction "E_3") (pintype "passive"))
      (node (ref "R5") (pin "2") (pinfunction "2_2") (pintype "passive"))
    )
    (net (code "17") (name "/H{slash}2OutNet6") (class "Default")
      (node (ref "Q6") (pin "2") (pinfunction "C_2") (pintype "passive"))
      (node (ref "R6") (pin "1") (pinfunction "1_1") (pintype "passive"))
    )
    (net (code "18") (name "/NEG_DIFF_OUT") (class "Default")
      (node (ref "CC6") (pin "2") (pinfunction "2_2") (pintype "passive"))
      (node (ref "Q18") (pin "2") (pinfunction "B_2") (pintype "passive"))
      (node (ref "Q38") (pin "3") (pinfunction "C_3") (pintype "passive"))
      (node (ref "RVC2") (pin "1") (pinfunction "A_1") (pintype "passive"))
      (node (ref "RVC2") (pin "2") (pinfunction "B_2") (pintype "passive"))
      (node (ref "TP8") (pin "1") (pintype "passive"))
    )
    (net (code "19") (name "/POS_DIFF_OUT") (class "Default")
      (node (ref "CC5") (pin "1") (pinfunction "1_1") (pintype "passive"))
      (node (ref "Q17") (pin "2") (pinfunction "B_2") (pintype "passive"))
      (node (ref "Q37") (pin "3") (pinfunction "C_3") (pintype "passive"))
      (node (ref "RVC1") (pin "1") (pinfunction "A_1") (pintype "passive"))
      (node (ref "RVC1") (pin "2") (pinfunction "B_2") (pintype "passive"))
      (node (ref "TP7") (pin "1") (pintype "passive"))
    )
    (net (code "20") (name "/VBM1") (class "Default")
      (node (ref "CC2") (pin "2") (pinfunction "2_2") (pintype "passive"))
      (node (ref "DZ1") (pin "1") (pinfunction "A_1") (pintype "passive"))
      (node (ref "JU3") (pin "1") (pinfunction "C1_1") (pintype "passive"))
      (node (ref "Q19") (pin "2") (pinfunction "C_2") (pintype "passive"))
      (node (ref "R21") (pin "2") (pinfunction "2_2") (pintype "passive"))
    )
    (net (code "21") (name "/VBM2") (class "Default")
      (node (ref "CC2") (pin "1") (pinfunction "1_1") (pintype "passive"))
      (node (ref "DZ2") (pin "2") (pinfunction "K_2") (pintype "passive"))
      (node (ref "JU4") (pin "1") (pinfunction "C1_1") (pintype "passive"))
      (node (ref "Q20") (pin "2") (pinfunction "C_2") (pintype "passive"))
      (node (ref "R22") (pin "1") (pinfunction "1_1") (pintype "passive"))
    )
    (net (code "22") (name "GND") (class "Default")
      (node (ref "B1") (pin "2") (pinfunction "2_2") (pintype "passive"))
      (node (ref "B2") (pin "2") (pinfunction "2_2") (pintype "passive"))
      (node (ref "B3") (pin "2") (pinfunction "2_2") (pintype "passive"))
      (node (ref "B4") (pin "2") (pinfunction "2_2") (pintype "passive"))
      (node (ref "BO") (pin "2") (pinfunction "2_2") (pintype "passive"))
      (node (ref "CAF") (pin "1") (pinfunction "1_1") (pintype "passive"))
      (node (ref "CCF32") (pin "1") (pinfunction "1_1") (pintype "passive"))
      (node (ref "CF1") (pin "2") (pinfunction "2_2") (pintype "passive"))
      (node (ref "CF10") (pin "1") (pinfunction "1_1") (pintype "passive"))
      (node (ref "CF11") (pin "1") (pinfunction "1_1") (pintype "passive"))
      (node (ref "CF12") (pin "1") (pinfunction "1_1") (pintype "passive"))
      (node (ref "CF2") (pin "1") (pinfunction "1_1") (pintype "passive"))
      (node (ref "CF3") (pin "2") (pinfunction "2_2") (pintype "passive"))
      (node (ref "CF31") (pin "2") (pinfunction "2_2") (pintype "passive"))
      (node (ref "CF33") (pin "1") (pinfunction "1_1") (pintype "passive"))
      (node (ref "CF34") (pin "1") (pinfunction "1_1") (pintype "passive"))
      (node (ref "CF35") (pin "2") (pinfunction "2_2") (pintype "passive"))
      (node (ref "CF36") (pin "1") (pinfunction "1_1") (pintype "passive"))
      (node (ref "CF37") (pin "1") (pinfunction "1_1") (pintype "passive"))
      (node (ref "CF38") (pin "2") (pinfunction "2_2") (pintype "passive"))
      (node (ref "CF39") (pin "2") (pinfunction "2_2") (pintype "passive"))
      (node (ref "CF4") (pin "1") (pinfunction "1_1") (pintype "passive"))
      (node (ref "CF40") (pin "1") (pinfunction "1_1") (pintype "passive"))
      (node (ref "CF5") (pin "1") (pinfunction "1_1") (pintype "passive"))
      (node (ref "CF6") (pin "2") (pinfunction "2_2") (pintype "passive"))
      (node (ref "CF7") (pin "1") (pinfunction "1_1") (pintype "passive"))
      (node (ref "CF8") (pin "2") (pinfunction "2_2") (pintype "passive"))
      (node (ref "CF9") (pin "2") (pinfunction "2_2") (pintype "passive"))
      (node (ref "D32") (pin "2") (pinfunction "A_2") (pintype "passive"))
      (node (ref "D34") (pin "1") (pinfunction "K_1") (pintype "passive"))
      (node (ref "IC1") (pin "2") (pinfunction "GND_2") (pintype "passive"))
      (node (ref "IC2") (pin "1") (pinfunction "GND_1") (pintype "passive"))
      (node (ref "JI") (pin "1") (pinfunction "1_1") (pintype "passive"))
      (node (ref "JI") (pin "2") (pinfunction "2_2") (pintype "passive"))
      (node (ref "JU1") (pin "3") (pinfunction "C3_3") (pintype "passive"))
      (node (ref "JU2") (pin "3") (pinfunction "C3_3") (pintype "passive"))
      (node (ref "JU3") (pin "3") (pinfunction "C3_3") (pintype "passive"))
      (node (ref "JU4") (pin "3") (pinfunction "C3_3") (pintype "passive"))
      (node (ref "Q17") (pin "3") (pinfunction "C_3") (pintype "passive"))
      (node (ref "Q18") (pin "3") (pinfunction "C_3") (pintype "passive"))
      (node (ref "R37") (pin "2") (pintype "passive"))
      (node (ref "R38") (pin "2") (pintype "passive"))
      (node (ref "RIOF") (pin "2") (pinfunction "2_2") (pintype "passive"))
      (node (ref "TPGND") (pin "1") (pintype "passive"))
    )
    (net (code "23") (name "Net-(CAI-Pad1)") (class "Default")
      (node (ref "CAI") (pin "1") (pinfunction "1_1") (pintype "passive"))
      (node (ref "JI") (pin "3") (pinfunction "3_3") (pintype "passive"))
      (node (ref "TPIN") (pin "1") (pintype "passive"))
    )
    (net (code "24") (name "Net-(D3-A)") (class "Default")
      (node (ref "D3") (pin "2") (pinfunction "A_2") (pintype "passive"))
      (node (ref "JU1") (pin "2") (pinfunction "C2_2") (pintype "passive"))
    )
    (net (code "25") (name "Net-(D3-K)") (class "Default")
      (node (ref "CC3") (pin "1") (pinfunction "1_1") (pintype "passive"))
      (node (ref "D3") (pin "1") (pinfunction "K_1") (pintype "passive"))
      (node (ref "Q7") (pin "3") (pinfunction "B_3") (pintype "passive"))
    )
    (net (code "26") (name "Net-(D4-A)") (class "Default")
      (node (ref "CC4") (pin "2") (pinfunction "2_2") (pintype "passive"))
      (node (ref "D4") (pin "2") (pinfunction "A_2") (pintype "passive"))
      (node (ref "Q8") (pin "3") (pinfunction "B_3") (pintype "passive"))
    )
    (net (code "27") (name "Net-(D4-K)") (class "Default")
      (node (ref "D4") (pin "1") (pinfunction "K_1") (pintype "passive"))
      (node (ref "JU2") (pin "2") (pinfunction "C2_2") (pintype "passive"))
    )
    (net (code "28") (name "Net-(D5-A)") (class "Default")
      (node (ref "D5") (pin "2") (pinfunction "A_2") (pintype "passive"))
      (node (ref "Q9") (pin "3") (pinfunction "B_3") (pintype "passive"))
      (node (ref "R17") (pin "2") (pinfunction "2_2") (pintype "passive"))
    )
    (net (code "29") (name "Net-(D5-K)") (class "Default")
      (node (ref "D5") (pin "1") (pinfunction "K_1") (pintype "passive"))
      (node (ref "Q11") (pin "3") (pinfunction "C_3") (pintype "passive"))
    )
    (net (code "30") (name "Net-(D6-A)") (class "Default")
      (node (ref "D6") (pin "2") (pinfunction "A_2") (pintype "passive"))
      (node (ref "Q12") (pin "3") (pinfunction "C_3") (pintype "passive"))
    )
    (net (code "31") (name "Net-(D6-K)") (class "Default")
      (node (ref "D6") (pin "1") (pinfunction "K_1") (pintype "passive"))
      (node (ref "Q10") (pin "3") (pinfunction "B_3") (pintype "passive"))
      (node (ref "R18") (pin "1") (pinfunction "1_1") (pintype "passive"))
    )
    (net (code "32") (name "Net-(D31-A)") (class "Default")
      (node (ref "D31") (pin "2") (pinfunction "A_2") (pintype "passive"))
      (node (ref "D32") (pin "1") (pinfunction "K_1") (pintype "passive"))
    )
    (net (code "33") (name "Net-(D31-K)") (class "Default")
      (node (ref "CAF") (pin "2") (pinfunction "2_2") (pintype "passive"))
      (node (ref "D31") (pin "1") (pinfunction "K_1") (pintype "passive"))
      (node (ref "D33") (pin "2") (pinfunction "A_2") (pintype "passive"))
      (node (ref "RFB2") (pin "1") (pinfunction "1_1") (pintype "passive"))
    )
    (net (code "34") (name "Net-(D33-K)") (class "Default")
      (node (ref "D33") (pin "1") (pinfunction "K_1") (pintype "passive"))
      (node (ref "D34") (pin "2") (pinfunction "A_2") (pintype "passive"))
    )
    (net (code "35") (name "Net-(D35-A)") (class "Default")
      (node (ref "D35") (pin "2") (pinfunction "A_2") (pintype "passive"))
      (node (ref "Q35") (pin "1") (pinfunction "B_1") (pintype "passive"))
      (node (ref "R37") (pin "1") (pintype "passive"))
    )
    (net (code "36") (name "Net-(D35-K)") (class "Default")
      (node (ref "D35") (pin "1") (pinfunction "K_1") (pintype "passive"))
      (node (ref "D37") (pin "2") (pinfunction "A_2") (pintype "passive"))
    )
    (net (code "37") (name "Net-(D36-A)") (class "Default")
      (node (ref "D36") (pin "2") (pinfunction "A_2") (pintype "passive"))
      (node (ref "D38") (pin "1") (pinfunction "K_1") (pintype "passive"))
    )
    (net (code "38") (name "Net-(D36-K)") (class "Default")
      (node (ref "D36") (pin "1") (pinfunction "K_1") (pintype "passive"))
      (node (ref "R38") (pin "1") (pintype "passive"))
    )
    (net (code "39") (name "Net-(DZ1-K)") (class "Default")
      (node (ref "CC5") (pin "2") (pinfunction "2_2") (pintype "passive"))
      (node (ref "DZ1") (pin "2") (pinfunction "K_2") (pintype "passive"))
      (node (ref "JU1") (pin "1") (pinfunction "C1_1") (pintype "passive"))
      (node (ref "Q15") (pin "1") (pinfunction "E_1") (pintype "passive"))
    )
    (net (code "40") (name "Net-(DZ2-A)") (class "Default")
      (node (ref "CC6") (pin "1") (pinfunction "1_1") (pintype "passive"))
      (node (ref "DZ2") (pin "1") (pinfunction "A_1") (pintype "passive"))
      (node (ref "JU2") (pin "1") (pinfunction "C1_1") (pintype "passive"))
      (node (ref "Q16") (pin "2") (pinfunction "C_2") (pintype "passive"))
    )
    (net (code "41") (name "Net-(DZ3-A)") (class "Default")
      (node (ref "DZ3") (pin "1") (pinfunction "A_1") (pintype "passive"))
      (node (ref "Q17") (pin "1") (pinfunction "E_1") (pintype "passive"))
    )
    (net (code "42") (name "Net-(DZ3-K)") (class "Default")
      (node (ref "DZ3") (pin "2") (pinfunction "K_2") (pintype "passive"))
      (node (ref "Q15") (pin "3") (pinfunction "B_3") (pintype "passive"))
      (node (ref "R19") (pin "1") (pinfunction "1_1") (pintype "passive"))
    )
    (net (code "43") (name "Net-(DZ4-A)") (class "Default")
      (node (ref "DZ4") (pin "1") (pinfunction "A_1") (pintype "passive"))
      (node (ref "Q16") (pin "3") (pinfunction "B_3") (pintype "passive"))
      (node (ref "R20") (pin "2") (pinfunction "2_2") (pintype "passive"))
    )
    (net (code "44") (name "Net-(DZ4-K)") (class "Default")
      (node (ref "DZ4") (pin "2") (pinfunction "K_2") (pintype "passive"))
      (node (ref "Q18") (pin "1") (pinfunction "E_1") (pintype "passive"))
    )
    (net (code "45") (name "Net-(JU3-C2)") (class "Default")
      (node (ref "JU3") (pin "2") (pinfunction "C2_2") (pintype "passive"))
      (node (ref "R17") (pin "1") (pinfunction "1_1") (pintype "passive"))
    )
    (net (code "46") (name "Net-(JU4-C2)") (class "Default")
      (node (ref "JU4") (pin "2") (pinfunction "C2_2") (pintype "passive"))
      (node (ref "R18") (pin "2") (pinfunction "2_2") (pintype "passive"))
    )
    (net (code "47") (name "Net-(JU5-C1)") (class "Default")
      (node (ref "CC7") (pin "2") (pinfunction "2_2") (pintype "passive"))
      (node (ref "JU5") (pin "1") (pinfunction "C1_1") (pintype "passive"))
      (node (ref "RFB1") (pin "2") (pinfunction "2_2") (pintype "passive"))
    )
    (net (code "48") (name "Net-(LED1-PadK)") (class "Default")
      (node (ref "LED1") (pin "K") (pinfunction "K_K") (pintype "passive"))
      (node (ref "RL1") (pin "2") (pinfunction "2_2") (pintype "passive"))
    )
    (net (code "49") (name "Net-(LED2-PadK)") (class "Default")
      (node (ref "LED2") (pin "K") (pinfunction "K_K") (pintype "passive"))
      (node (ref "RL2") (pin "2") (pinfunction "2_2") (pintype "passive"))
    )
    (net (code "50") (name "Net-(Q1-B)") (class "Default")
      (node (ref "Q1") (pin "1") (pinfunction "B_1") (pintype "passive"))
      (node (ref "Q5") (pin "1") (pinfunction "B_1") (pintype "passive"))
      (node (ref "Q7") (pin "1") (pinfunction "E_1") (pintype "passive"))
      (node (ref "R9") (pin "2") (pinfunction "2_2") (pintype "passive"))
    )
    (net (code "51") (name "Net-(Q2-B)") (class "Default")
      (node (ref "Q2") (pin "1") (pinfunction "B_1") (pintype "passive"))
      (node (ref "Q6") (pin "1") (pinfunction "B_1") (pintype "passive"))
      (node (ref "Q8") (pin "1") (pinfunction "E_1") (pintype "passive"))
      (node (ref "R10") (pin "1") (pinfunction "1_1") (pintype "passive"))
    )
    (net (code "52") (name "Net-(Q3-B)") (class "Default")
      (node (ref "CC1") (pin "2") (pinfunction "2_2") (pintype "passive"))
      (node (ref "Q3") (pin "1") (pinfunction "B_1") (pintype "passive"))
      (node (ref "Q9") (pin "1") (pinfunction "E_1") (pintype "passive"))
      (node (ref "R11") (pin "2") (pinfunction "2_2") (pintype "passive"))
    )
    (net (code "53") (name "Net-(Q10-E)") (class "Default")
      (node (ref "CC1") (pin "1") (pinfunction "1_1") (pintype "passive"))
      (node (ref "Q10") (pin "1") (pinfunction "E_1") (pintype "passive"))
      (node (ref "Q4") (pin "1") (pinfunction "B_1") (pintype "passive"))
      (node (ref "R12") (pin "1") (pinfunction "1_1") (pintype "passive"))
    )
    (net (code "54") (name "Net-(Q11-B)") (class "Default")
      (node (ref "Q11") (pin "2") (pinfunction "B_2") (pintype "passive"))
      (node (ref "R13") (pin "1") (pinfunction "1_1") (pintype "passive"))
      (node (ref "R7") (pin "1") (pinfunction "1_1") (pintype "passive"))
    )
    (net (code "55") (name "Net-(Q12-B)") (class "Default")
      (node (ref "Q12") (pin "2") (pinfunction "B_2") (pintype "passive"))
      (node (ref "R14") (pin "2") (pinfunction "2_2") (pintype "passive"))
      (node (ref "R8") (pin "2") (pinfunction "2_2") (pintype "passive"))
    )
    (net (code "56") (name "Net-(Q15-C)") (class "Default")
      (node (ref "Q15") (pin "2") (pinfunction "C_2") (pintype "passive"))
      (node (ref "R15") (pin "1") (pinfunction "1_1") (pintype "passive"))
      (node (ref "TP3") (pin "1") (pintype "passive"))
    )
    (net (code "57") (name "Net-(Q16-E)") (class "Default")
      (node (ref "Q16") (pin "1") (pinfunction "E_1") (pintype "passive"))
      (node (ref "R16") (pin "1") (pinfunction "1_1") (pintype "passive"))
      (node (ref "TP4") (pin "1") (pintype "passive"))
    )
    (net (code "58") (name "Net-(Q19-B)") (class "Default")
      (node (ref "Q19") (pin "3") (pinfunction "B_3") (pintype "passive"))
      (node (ref "R21") (pin "1") (pinfunction "1_1") (pintype "passive"))
      (node (ref "RVMV") (pin "1") (pinfunction "A_1") (pintype "passive"))
    )
    (net (code "59") (name "Net-(Q19-E)") (class "Default")
      (node (ref "Q19") (pin "1") (pinfunction "E_1") (pintype "passive"))
      (node (ref "Q20") (pin "1") (pinfunction "E_1") (pintype "passive"))
      (node (ref "TPMIDMV") (pin "1") (pinfunction "C1_1") (pintype "passive"))
    )
    (net (code "60") (name "Net-(Q20-B)") (class "Default")
      (node (ref "Q20") (pin "3") (pinfunction "B_3") (pintype "passive"))
      (node (ref "R22") (pin "2") (pinfunction "2_2") (pintype "passive"))
      (node (ref "RMVM") (pin "1") (pinfunction "1_1") (pintype "passive"))
    )
    (net (code "61") (name "Net-(Q31-C)") (class "Default")
      (node (ref "Q31") (pin "3") (pinfunction "C_3") (pintype "passive"))
      (node (ref "R31") (pin "1") (pinfunction "1_1") (pintype "passive"))
    )
    (net (code "62") (name "Net-(Q31-E)") (class "Default")
      (node (ref "Q31") (pin "2") (pinfunction "E_2") (pintype "passive"))
      (node (ref "QI") (pin "3") (pinfunction "C2_3") (pintype "passive"))
      (node (ref "QI") (pin "4") (pinfunction "C2_4") (pintype "passive"))
    )
    (net (code "63") (name "Net-(Q32-C)") (class "Default")
      (node (ref "Q32") (pin "3") (pinfunction "C_3") (pintype "passive"))
      (node (ref "R32") (pin "1") (pinfunction "1_1") (pintype "passive"))
    )
    (net (code "64") (name "Net-(Q32-E)") (class "Default")
      (node (ref "Q32") (pin "2") (pinfunction "E_2") (pintype "passive"))
      (node (ref "QI") (pin "7") (pinfunction "C4_7") (pintype "passive"))
      (node (ref "QI") (pin "8") (pinfunction "C4_8") (pintype "passive"))
    )
    (net (code "65") (name "Net-(Q35-C)") (class "Default")
      (node (ref "Q35") (pin "3") (pinfunction "C_3") (pintype "passive"))
      (node (ref "QI") (pin "14") (pinfunction "E2_14") (pintype "passive"))
      (node (ref "QI") (pin "16") (pinfunction "E1_16") (pintype "passive"))
    )
    (net (code "66") (name "Net-(Q35-E)") (class "Default")
      (node (ref "Q35") (pin "2") (pinfunction "E_2") (pintype "passive"))
      (node (ref "RV1") (pin "3") (pinfunction "C_3") (pintype "passive"))
    )
    (net (code "67") (name "Net-(Q36-C)") (class "Default")
      (node (ref "Q36") (pin "3") (pinfunction "C_3") (pintype "passive"))
      (node (ref "QI") (pin "10") (pinfunction "E4_10") (pintype "passive"))
      (node (ref "QI") (pin "12") (pinfunction "E3_12") (pintype "passive"))
    )
    (net (code "68") (name "Net-(Q36-E)") (class "Default")
      (node (ref "Q36") (pin "2") (pinfunction "E_2") (pintype "passive"))
      (node (ref "RV2") (pin "3") (pinfunction "C_3") (pintype "passive"))
    )
    (net (code "69") (name "Net-(Q37-E)") (class "Default")
      (node (ref "Q37") (pin "2") (pinfunction "E_2") (pintype "passive"))
      (node (ref "QI") (pin "1") (pinfunction "C1_1") (pintype "passive"))
      (node (ref "QI") (pin "2") (pinfunction "C1_2") (pintype "passive"))
    )
    (net (code "70") (name "Net-(Q38-E)") (class "Default")
      (node (ref "Q38") (pin "2") (pinfunction "E_2") (pintype "passive"))
      (node (ref "QI") (pin "5") (pinfunction "C3_5") (pintype "passive"))
      (node (ref "QI") (pin "6") (pinfunction "C3_6") (pintype "passive"))
    )
    (net (code "71") (name "Net-(QIA-B1)") (class "Default")
      (node (ref "CAI") (pin "2") (pinfunction "2_2") (pintype "passive"))
      (node (ref "QI") (pin "15") (pinfunction "B1_15") (pintype "passive"))
      (node (ref "RIOF") (pin "1") (pinfunction "1_1") (pintype "passive"))
    )
    (net (code "72") (name "Net-(QIB-B2)") (class "Default")
      (node (ref "CC7") (pin "1") (pinfunction "1_1") (pintype "passive"))
      (node (ref "QI") (pin "13") (pinfunction "B2_13") (pintype "passive"))
      (node (ref "QI") (pin "9") (pinfunction "B4_9") (pintype "passive"))
      (node (ref "RFB1") (pin "1") (pinfunction "1_1") (pintype "passive"))
      (node (ref "RFB2") (pin "2") (pinfunction "2_2") (pintype "passive"))
    )
    (net (code "73") (name "Net-(R11-Pad1)") (class "Default")
      (node (ref "R11") (pin "1") (pinfunction "1_1") (pintype "passive"))
      (node (ref "R12") (pin "2") (pinfunction "2_2") (pintype "passive"))
    )
    (net (code "74") (name "Net-(RV1-A)") (class "Default")
      (node (ref "R33") (pin "2") (pintype "passive"))
      (node (ref "RV1") (pin "1") (pinfunction "A_1") (pintype "passive"))
      (node (ref "RV1") (pin "2") (pinfunction "B_2") (pintype "passive"))
      (node (ref "TP9") (pin "1") (pintype "passive"))
    )
    (net (code "75") (name "Net-(RV2-A)") (class "Default")
      (node (ref "R34") (pin "2") (pintype "passive"))
      (node (ref "RV2") (pin "1") (pinfunction "A_1") (pintype "passive"))
      (node (ref "RV2") (pin "2") (pinfunction "B_2") (pintype "passive"))
      (node (ref "TP10") (pin "1") (pintype "passive"))
    )
    (net (code "76") (name "Net-(RVC1-C)") (class "Default")
      (node (ref "R35") (pin "1") (pinfunction "1_1") (pintype "passive"))
      (node (ref "RVC1") (pin "3") (pinfunction "C_3") (pintype "passive"))
    )
    (net (code "77") (name "Net-(RVC2-C)") (class "Default")
      (node (ref "R36") (pin "1") (pinfunction "1_1") (pintype "passive"))
      (node (ref "RVC2") (pin "3") (pinfunction "C_3") (pintype "passive"))
    )
    (net (code "78") (name "Net-(RVMV-B)") (class "Default")
      (node (ref "RVMV") (pin "2") (pinfunction "B_2") (pintype "passive"))
      (node (ref "RVMV") (pin "3") (pinfunction "C_3") (pintype "passive"))
    )
    (net (code "79") (name "unconnected-(Q36-B-Pad1)") (class "Default")
      (node (ref "Q36") (pin "1") (pinfunction "B_1") (pintype "passive"))
    )
    (net (code "80") (name "unconnected-(QIC-B3-Pad11)") (class "Default")
      (node (ref "QI") (pin "11") (pinfunction "B3_11") (pintype "passive"))
    )
    (net (code "81") (name "unconnected-(R20-Pad1)") (class "Default")
      (node (ref "R20") (pin "1") (pinfunction "1_1") (pintype "passive"))
    )
    (net (code "82") (name "unconnected-(RMVM-Pad2)") (class "Default")
      (node (ref "RMVM") (pin "2") (pinfunction "2_2") (pintype "passive"))
    )
  )
)
